# All-in-one_Starter_Kit_for_Pico_2_V1_3.net
KiCad netlist of a schematic drawn in EAGLE
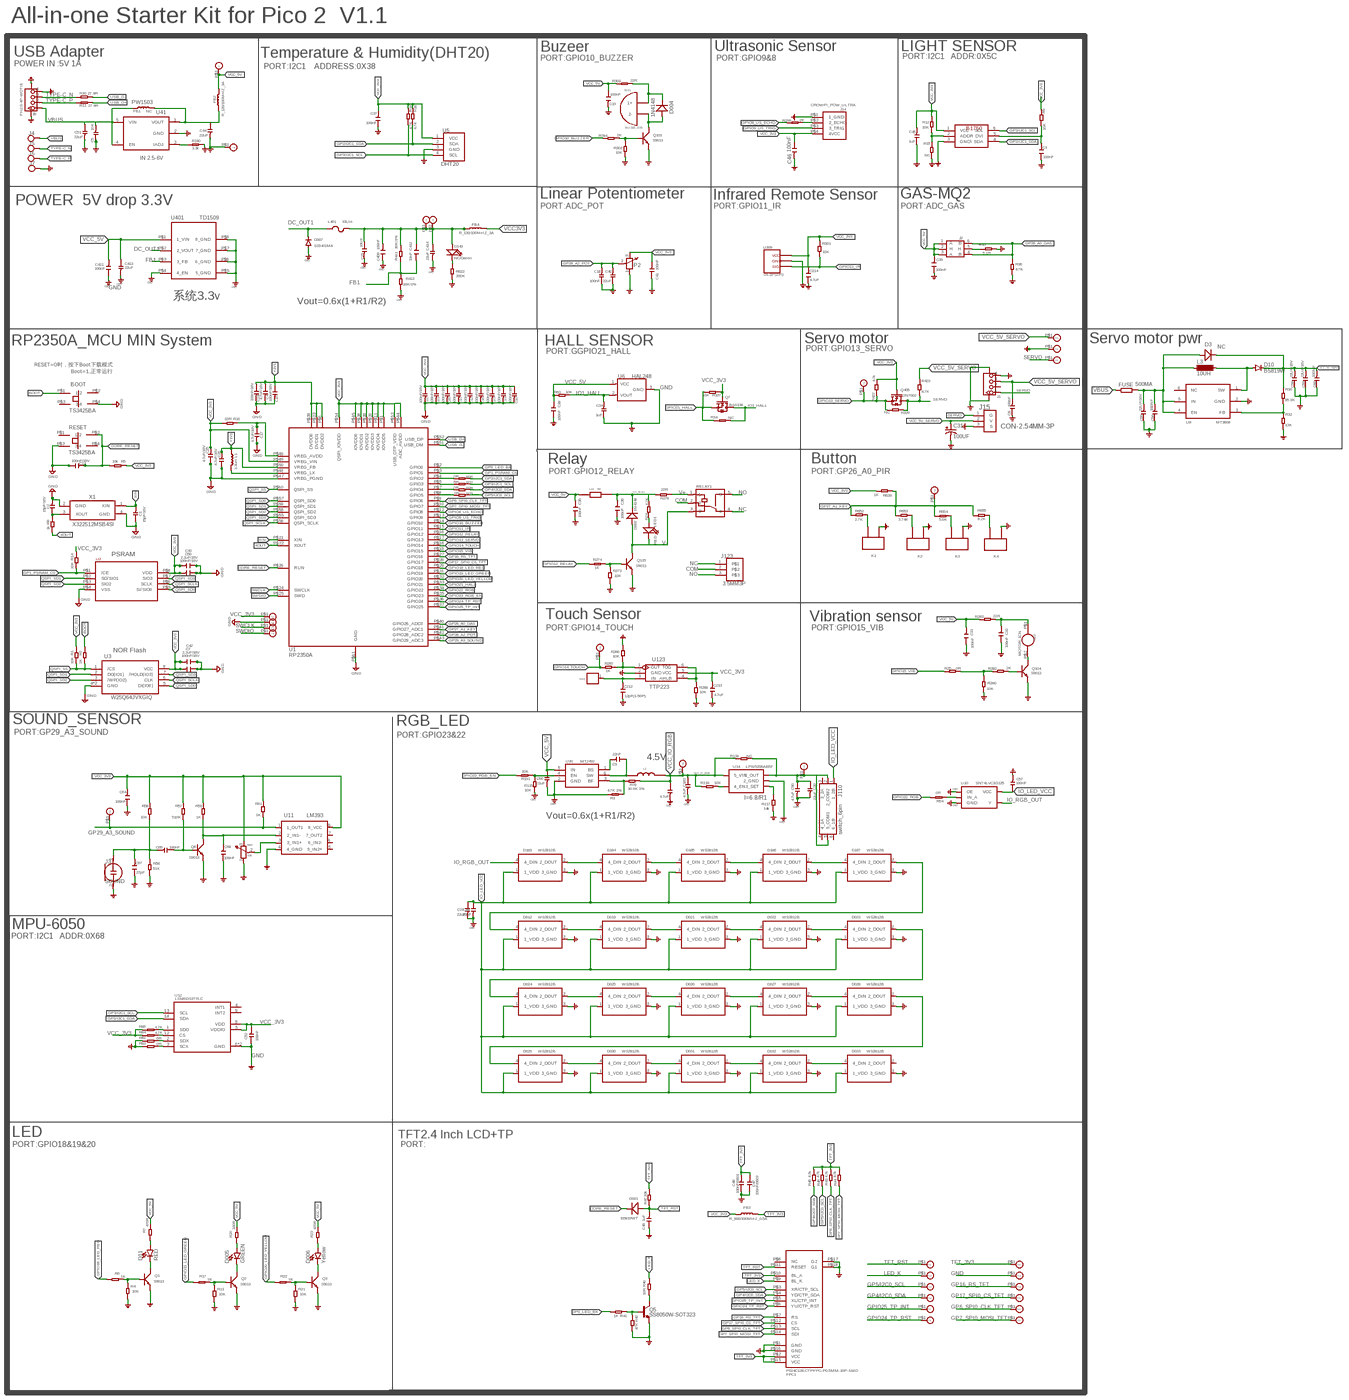
[diagram p0: schematic, sheet 1, overview]
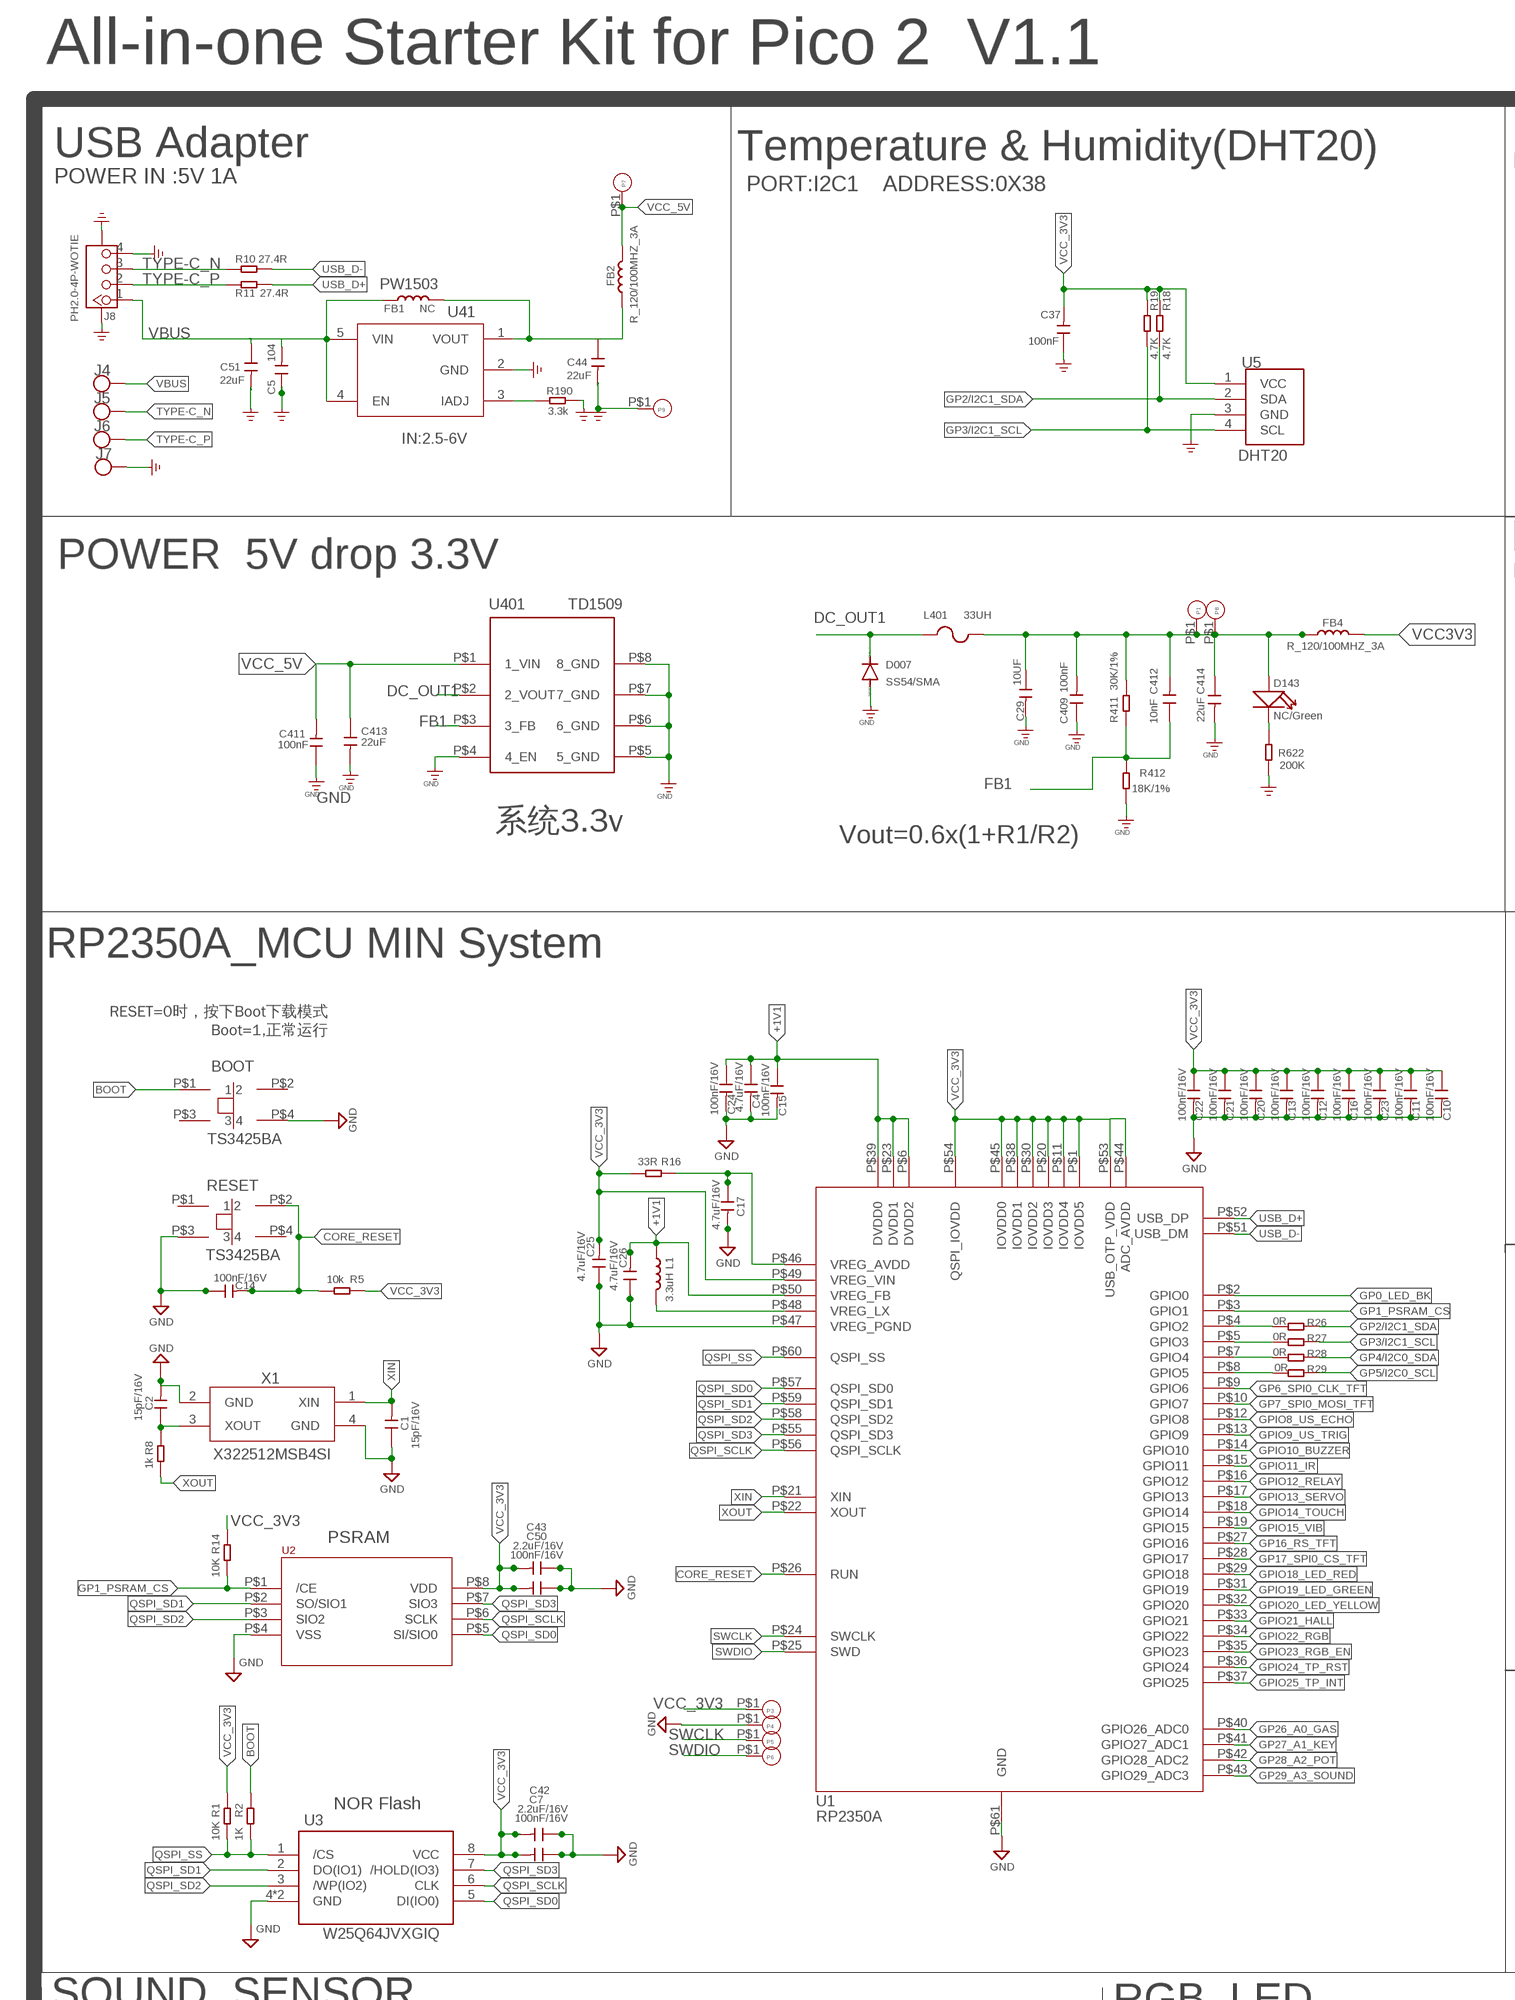
[diagram p1: schematic, sheet 1, part 1 of 4]
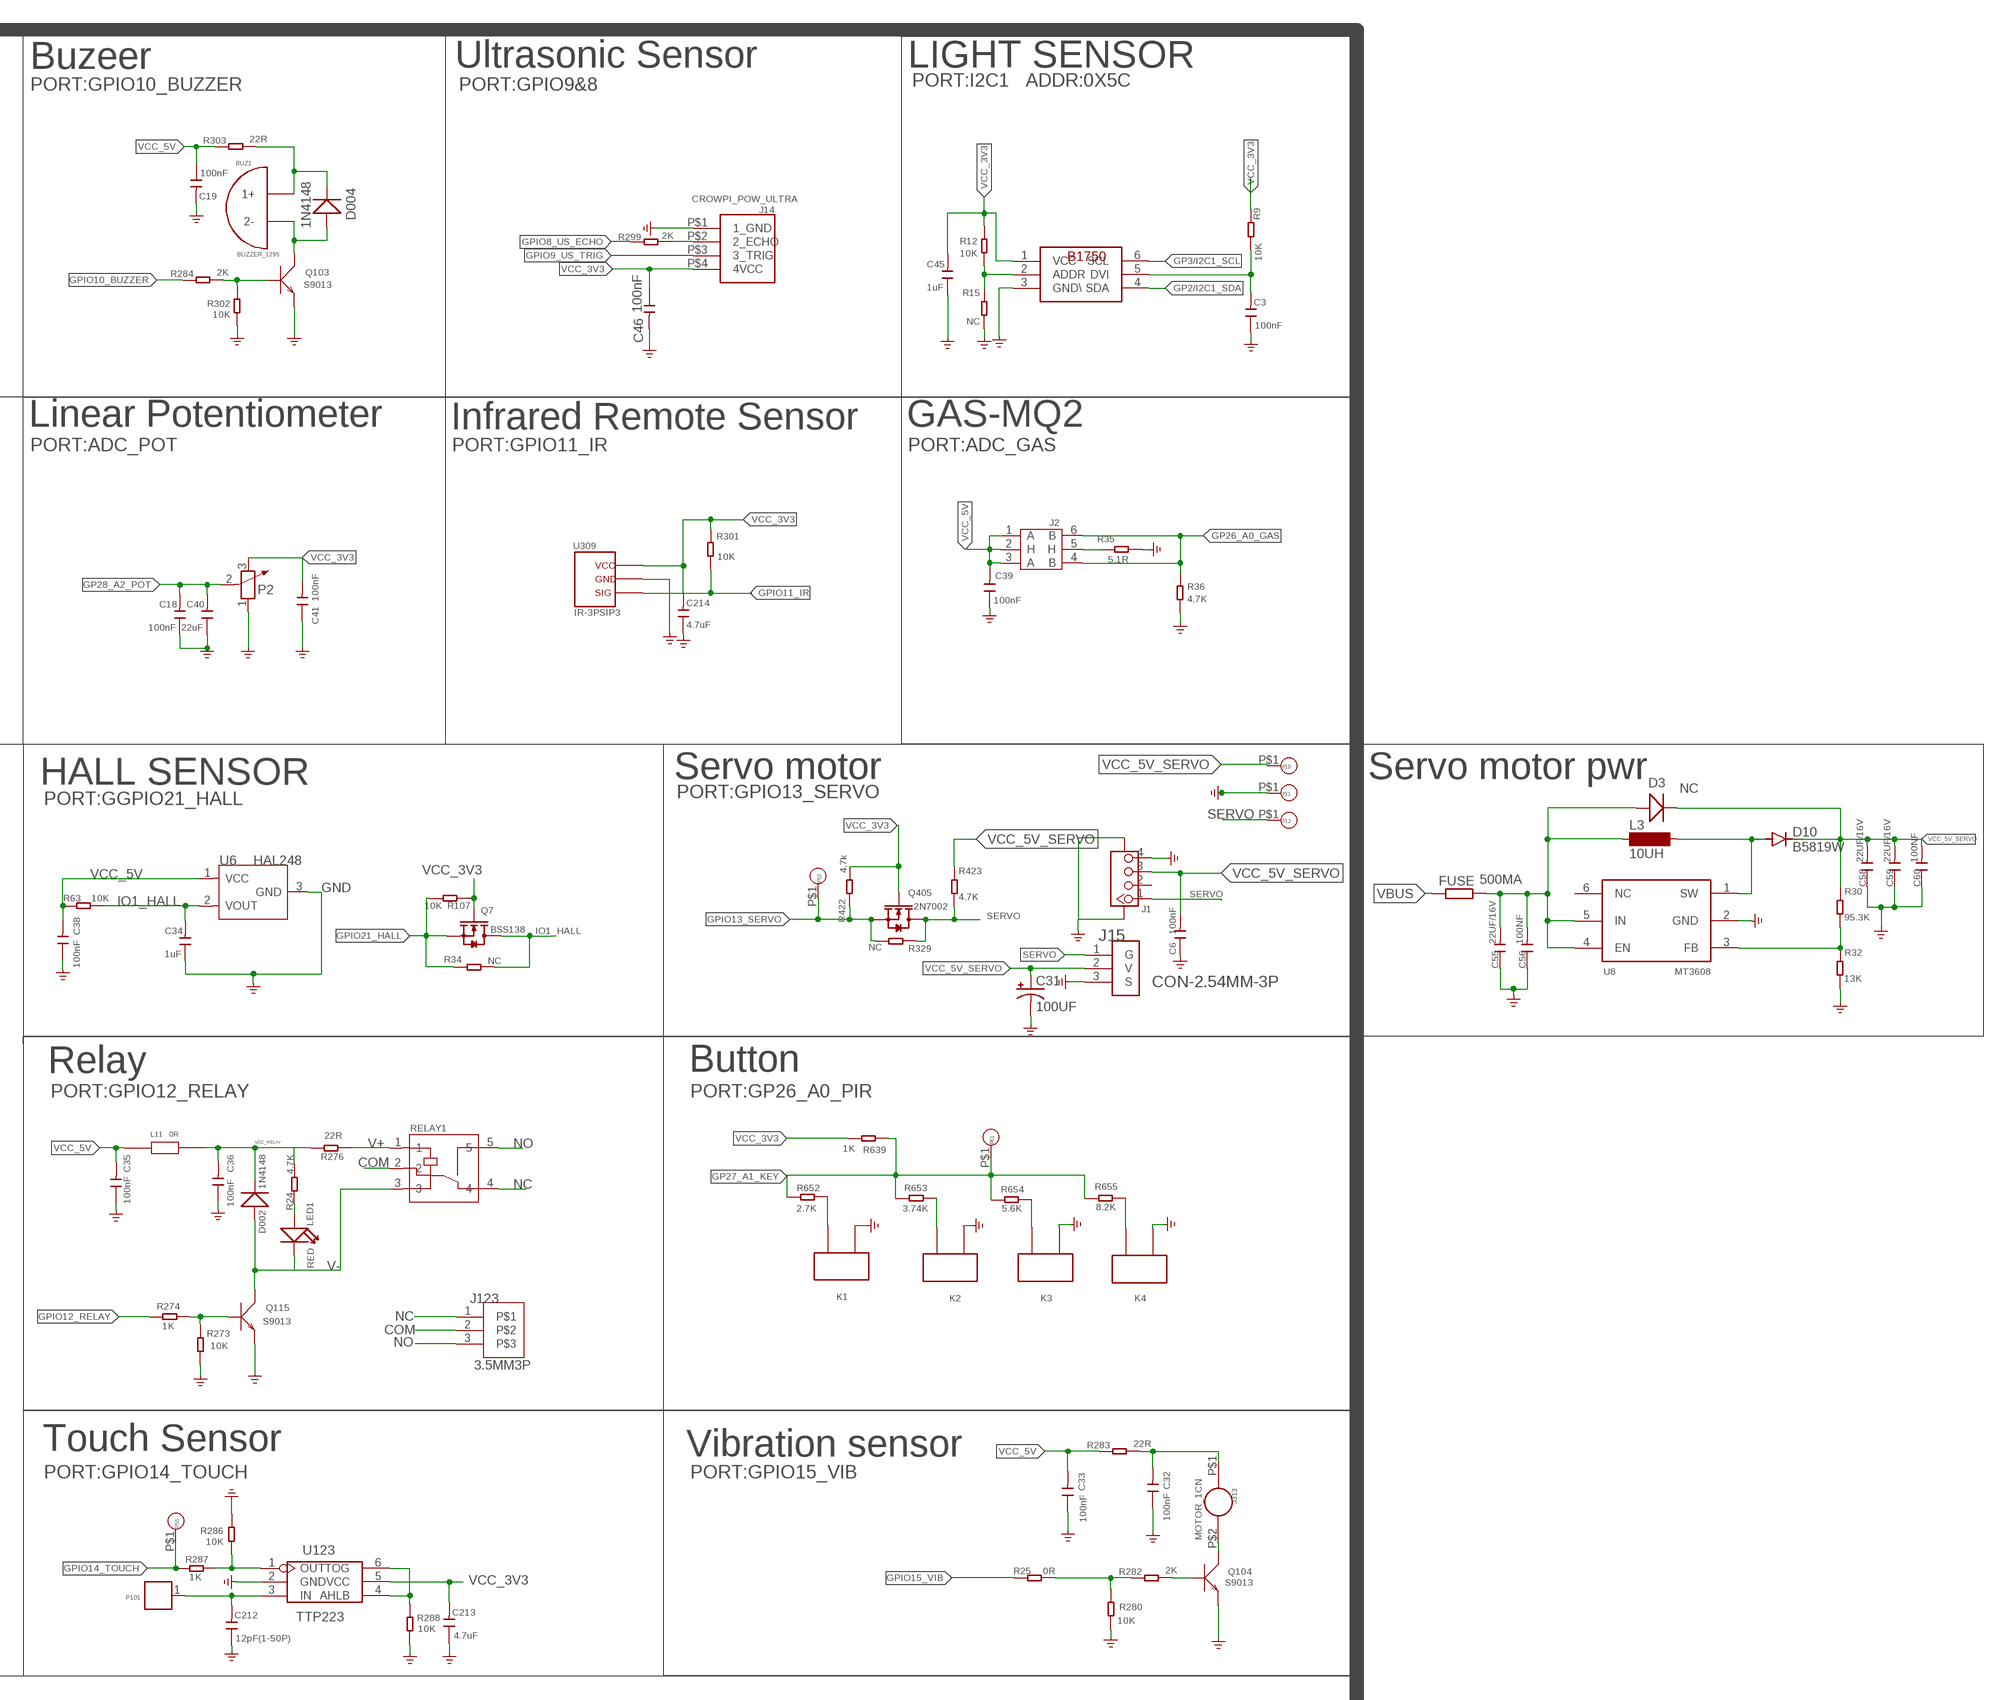
[diagram p2: schematic, sheet 1, part 2 of 4]
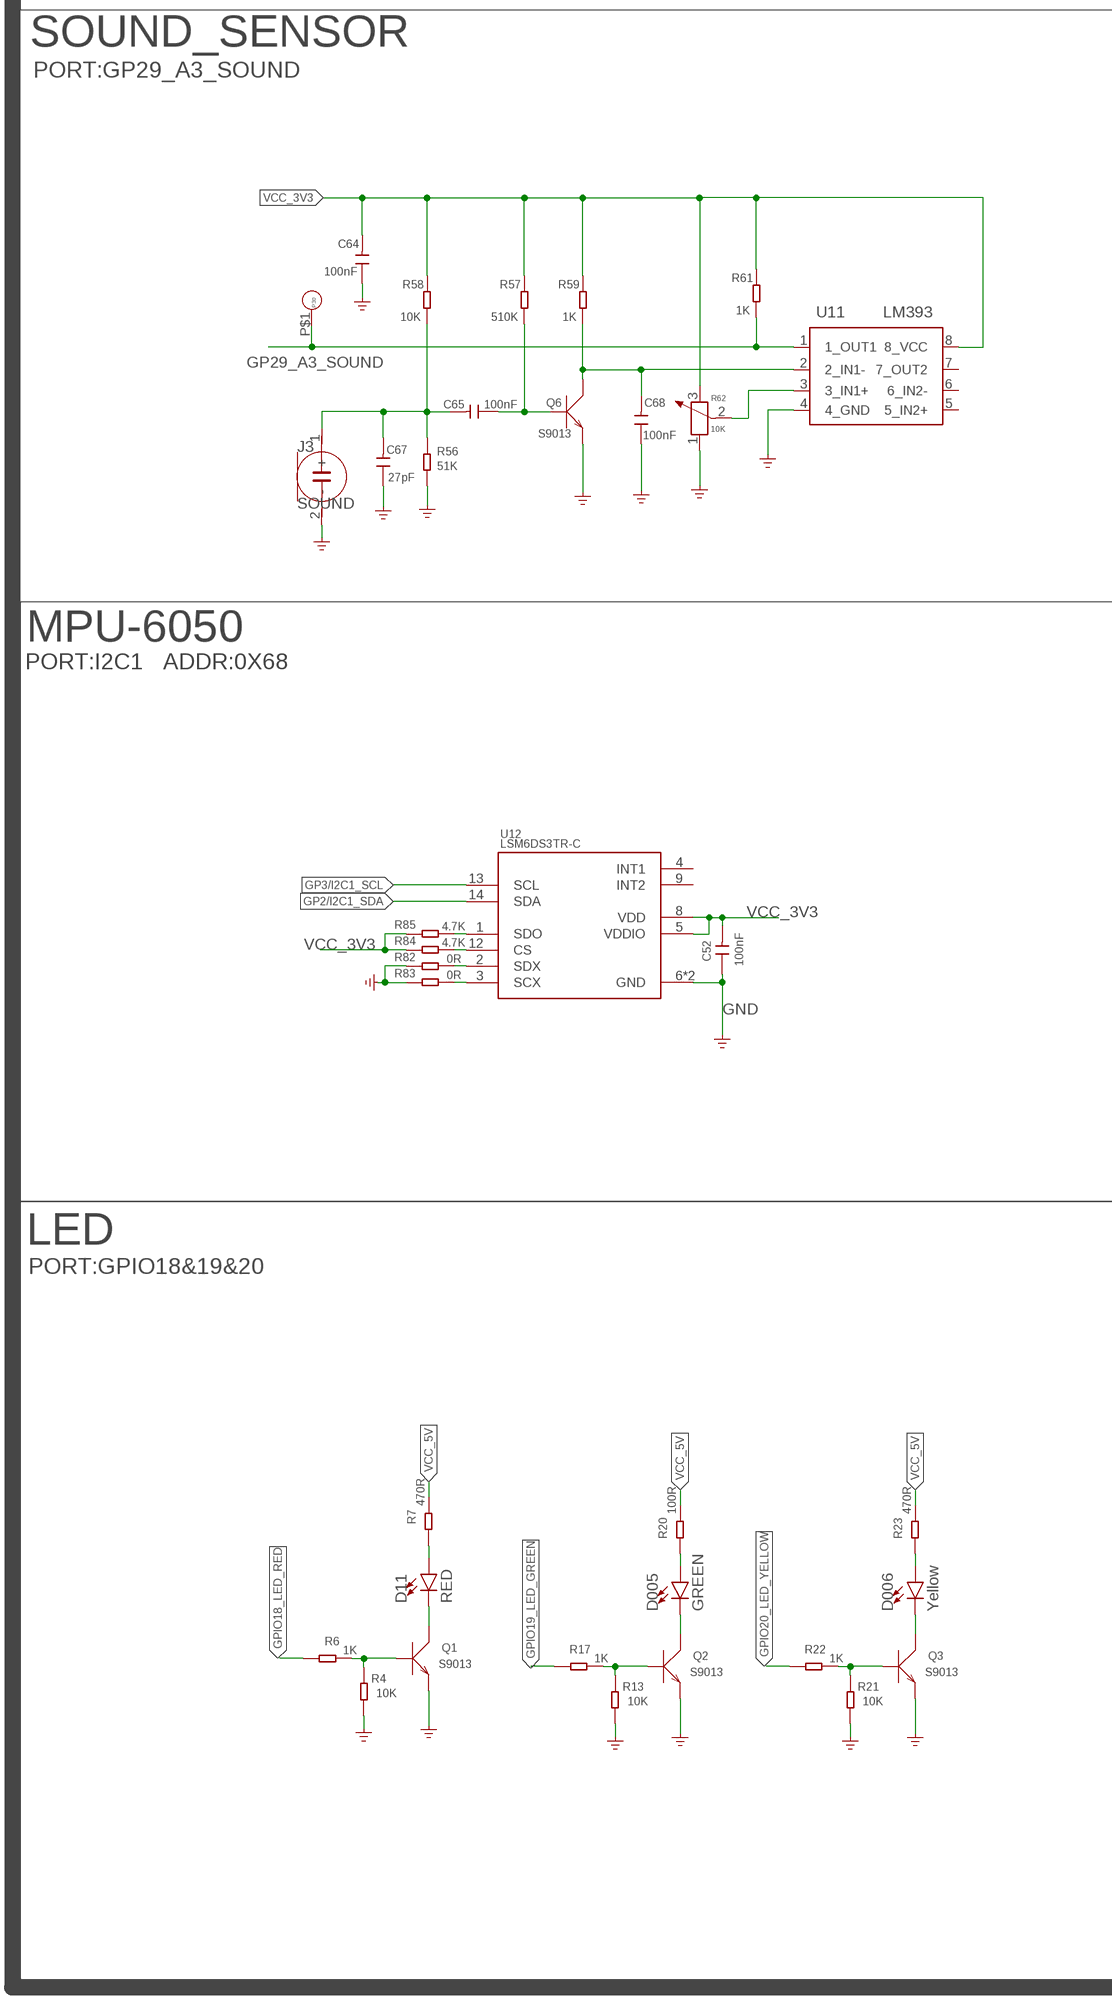
[diagram p3: schematic, sheet 1, part 3 of 4]
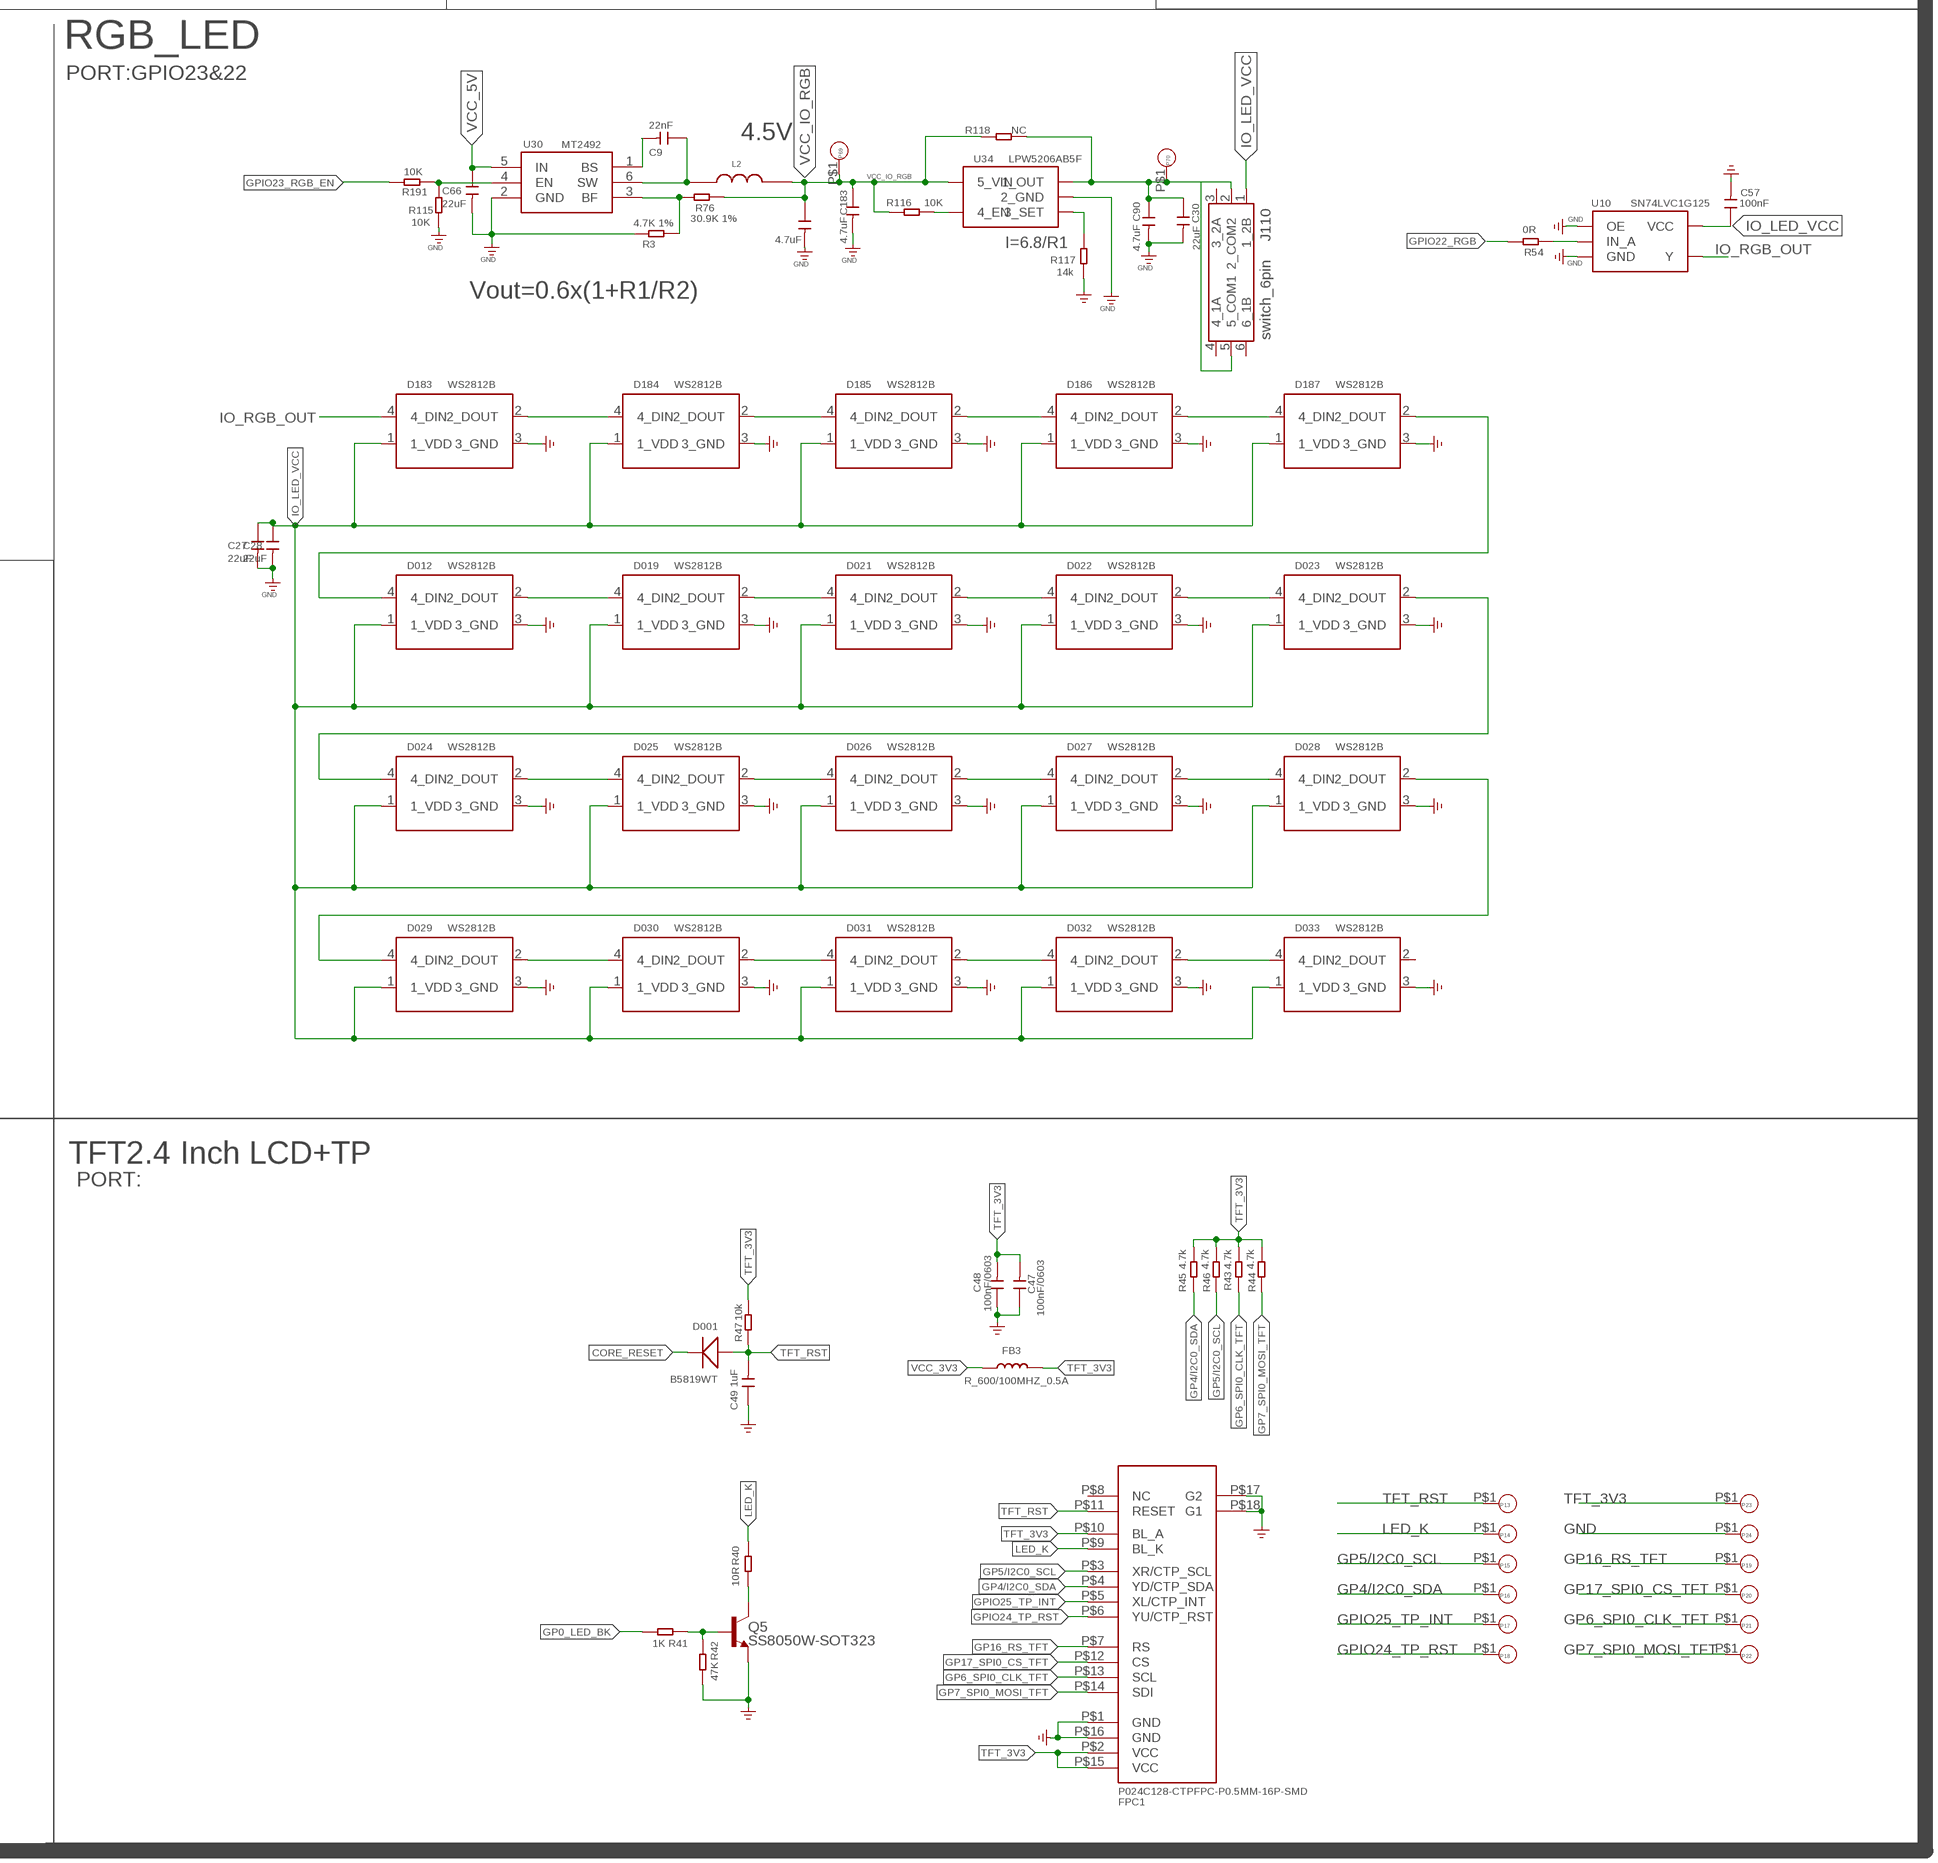
[diagram p4: schematic, sheet 1, part 4 of 4]

(export (version "E")
  (design (tool "Eeschema 10.0.6"))
  (components
    (comp (ref "BOOT")
      (value "TS3425BA")
      (footprint "eagle-import:SMD_KEY4.2_3._.2.5")
      (libsource (lib "eagle-import") (part "KEY"))
    )
    (comp (ref "BUZ1")
      (value "BUZZER_1295")
      (footprint "eagle-import:BUZZER-D12MM-DIP2")
      (libsource (lib "eagle-import") (part "BUZZERBUZZER_1295_DIP"))
    )
    (comp (ref "C1")
      (value "15pF/16V")
      (footprint "eagle-import:C0603")
      (libsource (lib "eagle-import") (part "CAPC0603"))
    )
    (comp (ref "C2")
      (value "15pF/16V")
      (footprint "eagle-import:C0603")
      (libsource (lib "eagle-import") (part "CAPC0603"))
    )
    (comp (ref "C3")
      (value "100nF")
      (footprint "eagle-import:C0603")
      (libsource (lib "eagle-import") (part "CAPC0603"))
    )
    (comp (ref "C4")
      (value "4.7uF/16V")
      (footprint "eagle-import:C0603")
      (libsource (lib "eagle-import") (part "CAPC0603"))
    )
    (comp (ref "C5")
      (value "104")
      (footprint "eagle-import:C0805")
      (libsource (lib "eagle-import") (part "CAPC0805"))
    )
    (comp (ref "C6")
      (value "100nF")
      (footprint "eagle-import:C0603")
      (libsource (lib "eagle-import") (part "CAPC0603"))
    )
    (comp (ref "C7")
      (value "100nF/16V")
      (footprint "eagle-import:C0603")
      (libsource (lib "eagle-import") (part "CAPC0603"))
    )
    (comp (ref "C8")
      (value "4.7uF")
      (footprint "eagle-import:C0603")
      (libsource (lib "eagle-import") (part "CAPC0603"))
    )
    (comp (ref "C9")
      (value "22nF")
      (footprint "eagle-import:C0603")
      (libsource (lib "eagle-import") (part "CAPC0603"))
    )
    (comp (ref "C10")
      (value "100nF/16V")
      (footprint "eagle-import:C0603")
      (libsource (lib "eagle-import") (part "CAPC0603"))
    )
    (comp (ref "C11")
      (value "100nF/16V")
      (footprint "eagle-import:C0603")
      (libsource (lib "eagle-import") (part "CAPC0603"))
    )
    (comp (ref "C12")
      (value "100nF/16V")
      (footprint "eagle-import:C0603")
      (libsource (lib "eagle-import") (part "CAPC0603"))
    )
    (comp (ref "C13")
      (value "100nF/16V")
      (footprint "eagle-import:C0603")
      (libsource (lib "eagle-import") (part "CAPC0603"))
    )
    (comp (ref "C14")
      (value "100nF/16V")
      (footprint "eagle-import:C0603")
      (libsource (lib "eagle-import") (part "CAPC0603"))
    )
    (comp (ref "C15")
      (value "100nF/16V")
      (footprint "eagle-import:C0603")
      (libsource (lib "eagle-import") (part "CAPC0603"))
    )
    (comp (ref "C16")
      (value "100nF/16V")
      (footprint "eagle-import:C0603")
      (libsource (lib "eagle-import") (part "CAPC0603"))
    )
    (comp (ref "C17")
      (value "4.7uF/16V")
      (footprint "eagle-import:C0603")
      (libsource (lib "eagle-import") (part "CAPC0603"))
    )
    (comp (ref "C18")
      (value "100nF")
      (footprint "eagle-import:C0603")
      (libsource (lib "eagle-import") (part "CAPC0603"))
    )
    (comp (ref "C19")
      (value "100nF")
      (footprint "eagle-import:C0603")
      (libsource (lib "eagle-import") (part "CAPC0603"))
    )
    (comp (ref "C20")
      (value "100nF/16V")
      (footprint "eagle-import:C0603")
      (libsource (lib "eagle-import") (part "CAPC0603"))
    )
    (comp (ref "C21")
      (value "100nF/16V")
      (footprint "eagle-import:C0603")
      (libsource (lib "eagle-import") (part "CAPC0603"))
    )
    (comp (ref "C22")
      (value "100nF/16V")
      (footprint "eagle-import:C0603")
      (libsource (lib "eagle-import") (part "CAPC0603"))
    )
    (comp (ref "C23")
      (value "100nF/16V")
      (footprint "eagle-import:C0603")
      (libsource (lib "eagle-import") (part "CAPC0603"))
    )
    (comp (ref "C24")
      (value "100nF/16V")
      (footprint "eagle-import:C0603")
      (libsource (lib "eagle-import") (part "CAPC0603"))
    )
    (comp (ref "C25")
      (value "4.7uF/16V")
      (footprint "eagle-import:C0603")
      (libsource (lib "eagle-import") (part "CAPC0603"))
    )
    (comp (ref "C26")
      (value "4.7uF/16V")
      (footprint "eagle-import:C0603")
      (libsource (lib "eagle-import") (part "CAPC0603"))
    )
    (comp (ref "C27")
      (value "22uF")
      (footprint "eagle-import:C0805")
      (libsource (lib "eagle-import") (part "CAPC0805"))
    )
    (comp (ref "C28")
      (value "22uF")
      (footprint "eagle-import:C0805")
      (libsource (lib "eagle-import") (part "CAPC0805"))
    )
    (comp (ref "C29")
      (value "10UF")
      (footprint "eagle-import:C0805")
      (libsource (lib "eagle-import") (part "CAPC0805"))
    )
    (comp (ref "C30")
      (value "22uF")
      (footprint "eagle-import:C0805")
      (libsource (lib "eagle-import") (part "CAPC0805"))
    )
    (comp (ref "C31")
      (value "100UF")
      (footprint "eagle-import:SANYO-OSCON_SMD_C6")
      (libsource (lib "eagle-import") (part "CPOL-USSANYO_SMD_C6"))
    )
    (comp (ref "C32")
      (value "100nF")
      (footprint "eagle-import:C0603")
      (libsource (lib "eagle-import") (part "CAPC0603"))
    )
    (comp (ref "C33")
      (value "100nF")
      (footprint "eagle-import:C0603")
      (libsource (lib "eagle-import") (part "CAPC0603"))
    )
    (comp (ref "C34")
      (value "1uF")
      (footprint "eagle-import:C0603")
      (libsource (lib "eagle-import") (part "CAPC0603"))
    )
    (comp (ref "C35")
      (value "100nF")
      (footprint "eagle-import:C0603")
      (libsource (lib "eagle-import") (part "CAPC0603"))
    )
    (comp (ref "C36")
      (value "100nF")
      (footprint "eagle-import:C0603")
      (libsource (lib "eagle-import") (part "CAPC0603"))
    )
    (comp (ref "C37")
      (value "100nF")
      (footprint "eagle-import:C0603")
      (libsource (lib "eagle-import") (part "CAPC0603"))
    )
    (comp (ref "C38")
      (value "100nF")
      (footprint "eagle-import:C0603")
      (libsource (lib "eagle-import") (part "CAPC0603"))
    )
    (comp (ref "C39")
      (value "100nF")
      (footprint "eagle-import:C0603")
      (libsource (lib "eagle-import") (part "CAPC0603"))
    )
    (comp (ref "C40")
      (value "22uF")
      (footprint "eagle-import:C0603")
      (libsource (lib "eagle-import") (part "CAPC0603"))
    )
    (comp (ref "C41")
      (value "100nF")
      (footprint "eagle-import:C0603")
      (libsource (lib "eagle-import") (part "CAPC0603"))
    )
    (comp (ref "C42")
      (value "2.2uF/16V")
      (footprint "eagle-import:C0603")
      (libsource (lib "eagle-import") (part "CAPC0603"))
    )
    (comp (ref "C43")
      (value "2.2uF/16V")
      (footprint "eagle-import:C0603")
      (libsource (lib "eagle-import") (part "CAPC0603"))
    )
    (comp (ref "C44")
      (value "22uF")
      (footprint "eagle-import:C0805")
      (libsource (lib "eagle-import") (part "CAPC0805"))
    )
    (comp (ref "C45")
      (value "1uF")
      (footprint "eagle-import:C0603")
      (libsource (lib "eagle-import") (part "CAPC0603"))
    )
    (comp (ref "C46")
      (value "100nF")
      (footprint "eagle-import:C0603")
      (libsource (lib "eagle-import") (part "CAPC0603"))
    )
    (comp (ref "C47")
      (value "100nF/0603")
      (footprint "eagle-import:C0603")
      (libsource (lib "eagle-import") (part "CAPC0603"))
    )
    (comp (ref "C48")
      (value "100nF/0603")
      (footprint "eagle-import:C0603")
      (libsource (lib "eagle-import") (part "CAPC0603"))
    )
    (comp (ref "C49")
      (value "1uF")
      (footprint "eagle-import:C0603")
      (libsource (lib "eagle-import") (part "CAPC0603"))
    )
    (comp (ref "C50")
      (value "100nF/16V")
      (footprint "eagle-import:C0603")
      (libsource (lib "eagle-import") (part "CAPC0603"))
    )
    (comp (ref "C51")
      (value "22uF")
      (footprint "eagle-import:C0805")
      (libsource (lib "eagle-import") (part "CAPC0805"))
    )
    (comp (ref "C52")
      (value "100nF")
      (footprint "eagle-import:C0603")
      (libsource (lib "eagle-import") (part "C-0603"))
    )
    (comp (ref "C55")
      (value "22UF/16V")
      (footprint "eagle-import:C0603")
      (libsource (lib "eagle-import") (part "CAP"))
    )
    (comp (ref "C56")
      (value "100NF")
      (footprint "eagle-import:C0603")
      (libsource (lib "eagle-import") (part "CAP"))
    )
    (comp (ref "C57")
      (value "100nF")
      (footprint "eagle-import:C0603")
      (libsource (lib "eagle-import") (part "CAPC0603"))
    )
    (comp (ref "C58")
      (value "22UF/16V")
      (footprint "eagle-import:C0603")
      (libsource (lib "eagle-import") (part "CAP"))
    )
    (comp (ref "C59")
      (value "22UF/16V")
      (footprint "eagle-import:C0603")
      (libsource (lib "eagle-import") (part "CAP"))
    )
    (comp (ref "C60")
      (value "100NF")
      (footprint "eagle-import:C0603")
      (libsource (lib "eagle-import") (part "CAP"))
    )
    (comp (ref "C64")
      (value "100nF")
      (footprint "eagle-import:C0603")
      (libsource (lib "eagle-import") (part "CAPC0603"))
    )
    (comp (ref "C65")
      (value "100nF")
      (footprint "eagle-import:C0603")
      (libsource (lib "eagle-import") (part "CAPC0603"))
    )
    (comp (ref "C66")
      (value "22uF")
      (footprint "eagle-import:C0805")
      (libsource (lib "eagle-import") (part "CAPC0805"))
    )
    (comp (ref "C67")
      (value "27pF")
      (footprint "eagle-import:C0603")
      (libsource (lib "eagle-import") (part "CAPC0603"))
    )
    (comp (ref "C68")
      (value "100nF")
      (footprint "eagle-import:C0603")
      (libsource (lib "eagle-import") (part "CAPC0603"))
    )
    (comp (ref "C90")
      (value "4.7uF")
      (footprint "eagle-import:C0603")
      (libsource (lib "eagle-import") (part "CAPC0603"))
    )
    (comp (ref "C183")
      (value "4.7uF")
      (footprint "eagle-import:C0603")
      (libsource (lib "eagle-import") (part "CAPC0603"))
    )
    (comp (ref "C212")
      (value "12pF(1-50P)")
      (footprint "eagle-import:C0603")
      (libsource (lib "eagle-import") (part "CAPC0603"))
    )
    (comp (ref "C213")
      (value "4.7uF")
      (footprint "eagle-import:C0603")
      (libsource (lib "eagle-import") (part "CAPC0603"))
    )
    (comp (ref "C214")
      (value "4.7uF")
      (footprint "eagle-import:C0603")
      (libsource (lib "eagle-import") (part "CAPC0603"))
    )
    (comp (ref "C409")
      (value "100nF")
      (footprint "eagle-import:C0603")
      (libsource (lib "eagle-import") (part "CAPC0603"))
    )
    (comp (ref "C411")
      (value "100nF")
      (footprint "eagle-import:C0603")
      (libsource (lib "eagle-import") (part "CAPC0603"))
    )
    (comp (ref "C412")
      (value "10nF")
      (footprint "eagle-import:C0603")
      (libsource (lib "eagle-import") (part "CAPC0603"))
    )
    (comp (ref "C413")
      (value "22uF")
      (footprint "eagle-import:C0805")
      (libsource (lib "eagle-import") (part "CAPC0805"))
    )
    (comp (ref "C414")
      (value "22uF")
      (footprint "eagle-import:C0805")
      (libsource (lib "eagle-import") (part "CAPC0805"))
    )
    (comp (ref "D001")
      (value "B5819WT")
      (footprint "eagle-import:D_SOD523")
      (libsource (lib "eagle-import") (part "DIODE0603"))
    )
    (comp (ref "D002")
      (value "1N4148")
      (footprint "eagle-import:D_SOD123")
      (libsource (lib "eagle-import") (part "Crowtail_Starter_DIODE1206"))
    )
    (comp (ref "D3")
      (value "NC")
      (footprint "eagle-import:D_SOD123FL")
      (libsource (lib "eagle-import") (part "DIODE"))
    )
    (comp (ref "D004")
      (value "1N4148")
      (footprint "eagle-import:D_SOD123")
      (libsource (lib "eagle-import") (part "Crowtail_Starter_DIODE1206"))
    )
    (comp (ref "D005")
      (value "GREEN")
      (footprint "eagle-import:LED-8MM")
      (libsource (lib "eagle-import") (part "LED"))
    )
    (comp (ref "D006")
      (value "Yellow")
      (footprint "eagle-import:LED-8MM")
      (libsource (lib "eagle-import") (part "LED"))
    )
    (comp (ref "D007")
      (value "SS54/SMA")
      (footprint "eagle-import:DIODE_DO-214AC")
      (libsource (lib "eagle-import") (part "DIODE_DIODE-DO-214AC"))
    )
    (comp (ref "D10")
      (value "B5819W")
      (footprint "eagle-import:SOD-123_MINI-SMA")
      (libsource (lib "eagle-import") (part "CGRM400-G1"))
    )
    (comp (ref "D11")
      (value "RED")
      (footprint "eagle-import:LED-8MM")
      (libsource (lib "eagle-import") (part "LED"))
    )
    (comp (ref "D012")
      (value "WS2812B")
      (footprint "eagle-import:LED_RGB_WS2812_3535")
      (libsource (lib "eagle-import") (part "LED_RGB_WS2812_3535"))
    )
    (comp (ref "D019")
      (value "WS2812B")
      (footprint "eagle-import:LED_RGB_WS2812_3535")
      (libsource (lib "eagle-import") (part "LED_RGB_WS2812_3535"))
    )
    (comp (ref "D021")
      (value "WS2812B")
      (footprint "eagle-import:LED_RGB_WS2812_3535")
      (libsource (lib "eagle-import") (part "LED_RGB_WS2812_3535"))
    )
    (comp (ref "D022")
      (value "WS2812B")
      (footprint "eagle-import:LED_RGB_WS2812_3535")
      (libsource (lib "eagle-import") (part "LED_RGB_WS2812_3535"))
    )
    (comp (ref "D023")
      (value "WS2812B")
      (footprint "eagle-import:LED_RGB_WS2812_3535")
      (libsource (lib "eagle-import") (part "LED_RGB_WS2812_3535"))
    )
    (comp (ref "D024")
      (value "WS2812B")
      (footprint "eagle-import:LED_RGB_WS2812_3535")
      (libsource (lib "eagle-import") (part "LED_RGB_WS2812_3535"))
    )
    (comp (ref "D025")
      (value "WS2812B")
      (footprint "eagle-import:LED_RGB_WS2812_3535")
      (libsource (lib "eagle-import") (part "LED_RGB_WS2812_3535"))
    )
    (comp (ref "D026")
      (value "WS2812B")
      (footprint "eagle-import:LED_RGB_WS2812_3535")
      (libsource (lib "eagle-import") (part "LED_RGB_WS2812_3535"))
    )
    (comp (ref "D027")
      (value "WS2812B")
      (footprint "eagle-import:LED_RGB_WS2812_3535")
      (libsource (lib "eagle-import") (part "LED_RGB_WS2812_3535"))
    )
    (comp (ref "D028")
      (value "WS2812B")
      (footprint "eagle-import:LED_RGB_WS2812_3535")
      (libsource (lib "eagle-import") (part "LED_RGB_WS2812_3535"))
    )
    (comp (ref "D029")
      (value "WS2812B")
      (footprint "eagle-import:LED_RGB_WS2812_3535")
      (libsource (lib "eagle-import") (part "LED_RGB_WS2812_3535"))
    )
    (comp (ref "D030")
      (value "WS2812B")
      (footprint "eagle-import:LED_RGB_WS2812_3535")
      (libsource (lib "eagle-import") (part "LED_RGB_WS2812_3535"))
    )
    (comp (ref "D031")
      (value "WS2812B")
      (footprint "eagle-import:LED_RGB_WS2812_3535")
      (libsource (lib "eagle-import") (part "LED_RGB_WS2812_3535"))
    )
    (comp (ref "D032")
      (value "WS2812B")
      (footprint "eagle-import:LED_RGB_WS2812_3535")
      (libsource (lib "eagle-import") (part "LED_RGB_WS2812_3535"))
    )
    (comp (ref "D033")
      (value "WS2812B")
      (footprint "eagle-import:LED_RGB_WS2812_3535")
      (libsource (lib "eagle-import") (part "LED_RGB_WS2812_3535"))
    )
    (comp (ref "D143")
      (value "NC/Green")
      (footprint "eagle-import:LED_0603_SMT")
      (libsource (lib "eagle-import") (part "LED_0603_SMT"))
    )
    (comp (ref "D183")
      (value "WS2812B")
      (footprint "eagle-import:LED_RGB_WS2812_3535")
      (libsource (lib "eagle-import") (part "LED_RGB_WS2812_3535"))
    )
    (comp (ref "D184")
      (value "WS2812B")
      (footprint "eagle-import:LED_RGB_WS2812_3535")
      (libsource (lib "eagle-import") (part "LED_RGB_WS2812_3535"))
    )
    (comp (ref "D185")
      (value "WS2812B")
      (footprint "eagle-import:LED_RGB_WS2812_3535")
      (libsource (lib "eagle-import") (part "LED_RGB_WS2812_3535"))
    )
    (comp (ref "D186")
      (value "WS2812B")
      (footprint "eagle-import:LED_RGB_WS2812_3535")
      (libsource (lib "eagle-import") (part "LED_RGB_WS2812_3535"))
    )
    (comp (ref "D187")
      (value "WS2812B")
      (footprint "eagle-import:LED_RGB_WS2812_3535")
      (libsource (lib "eagle-import") (part "LED_RGB_WS2812_3535"))
    )
    (comp (ref "FB1")
      (value "NC")
      (footprint "eagle-import:L0805")
      (libsource (lib "eagle-import") (part "R_120/100MHZ_3A"))
    )
    (comp (ref "FB2")
      (value "R_120/100MHZ_3A")
      (footprint "eagle-import:L0805")
      (libsource (lib "eagle-import") (part "R_120/100MHZ_3A"))
    )
    (comp (ref "FB3")
      (value "R_600/100MHZ_0.5A")
      (footprint "eagle-import:L0603")
      (libsource (lib "eagle-import") (part "R_600/100MHZ_0.5A"))
    )
    (comp (ref "FB4")
      (value "R_120/100MHZ_3A")
      (footprint "eagle-import:L0805")
      (libsource (lib "eagle-import") (part "R_120/100MHZ_3A"))
    )
    (comp (ref "FPC1")
      (value "P024C128-CTPFPC-P0.5MM-16P-SMD")
      (footprint "eagle-import:FPC-P0.5MM-16P-SMD")
      (libsource (lib "eagle-import") (part "P024C128-CTPFPC-P0.5MM-16P-SMD"))
    )
    (comp (ref "FUSE")
      (value "500MA")
      (footprint "eagle-import:R0805")
      (libsource (lib "eagle-import") (part "R-EU_R0805"))
    )
    (comp (ref "J1")
      (value "A_XBJ_CONNECTOR_TWIG-4P-2.0-SMD-FEMALE-REINFORCE90D")
      (footprint "eagle-import:A_XBJ_CONNECTOR_4P-SMD-2.0-90D")
      (libsource (lib "eagle-import") (part "A_XBJ_CONNECTOR_TWIG-4P-2.0-SMD-FEMALE-REINFORCE90D"))
    )
    (comp (ref "J2")
      (value "MQ-SOCKET")
      (footprint "eagle-import:MQ2")
      (libsource (lib "eagle-import") (part "MQ-SOCKET"))
    )
    (comp (ref "J3")
      (value "SOUND")
      (footprint "eagle-import:TEMPLATE_2P-D8.9MM")
      (libsource (lib "eagle-import") (part "TEMPLATE_MICROPHONE"))
    )
    (comp (ref "J4")
      (value "TP-SMDTP-SMD-2X4MM")
      (footprint "eagle-import:TP-SMD-2X4MM")
      (libsource (lib "eagle-import") (part "TP-SMDTP-SMD-2X4MM"))
    )
    (comp (ref "J5")
      (value "TP-SMDTP-SMD-2X4MM")
      (footprint "eagle-import:TP-SMD-2X4MM")
      (libsource (lib "eagle-import") (part "TP-SMDTP-SMD-2X4MM"))
    )
    (comp (ref "J6")
      (value "TP-SMDTP-SMD-2X4MM")
      (footprint "eagle-import:TP-SMD-2X4MM")
      (libsource (lib "eagle-import") (part "TP-SMDTP-SMD-2X4MM"))
    )
    (comp (ref "J7")
      (value "TP-SMDTP-SMD-2X4MM")
      (footprint "eagle-import:TP-SMD-2X4MM")
      (libsource (lib "eagle-import") (part "TP-SMDTP-SMD-2X4MM"))
    )
    (comp (ref "J8")
      (value "PH2.0-4P-WOTIE")
      (footprint "eagle-import:PH2.0-4P")
      (libsource (lib "eagle-import") (part "PH2.0-4P-WOTIE"))
    )
    (comp (ref "J14")
      (value "CROWPI_POW_ULTRA")
      (footprint "eagle-import:CROWPI_POW_ULTRA")
      (libsource (lib "eagle-import") (part "CROWPI_POW_ULTRA"))
    )
    (comp (ref "J15")
      (value "CON-2.54MM-3P")
      (footprint "eagle-import:CON-PZ-2.54MM-1_3P-WT")
      (libsource (lib "eagle-import") (part "CON-2.54MM-13P-WT-SG90"))
    )
    (comp (ref "J110")
      (value "switch_6pin")
      (footprint "eagle-import:SWITCH_6PIN_2P")
      (libsource (lib "eagle-import") (part "SWITCH_6PIN_2P"))
    )
    (comp (ref "J123")
      (value "3.5MM3P")
      (footprint "eagle-import:3.5MM_3P")
      (libsource (lib "eagle-import") (part "3.5MM3P"))
    )
    (comp (ref "J313")
      (value "MOTOR_1CN")
      (footprint "eagle-import:MOTOR_1CM")
      (libsource (lib "eagle-import") (part "MOTOR_1CN"))
    )
    (comp (ref "K1")
      (value "BUTTON_2P")
      (footprint "eagle-import:BUTTON_2P")
      (libsource (lib "eagle-import") (part "BUTTON_2P"))
    )
    (comp (ref "K2")
      (value "BUTTON_2P")
      (footprint "eagle-import:BUTTON_2P")
      (libsource (lib "eagle-import") (part "BUTTON_2P"))
    )
    (comp (ref "K3")
      (value "BUTTON_2P")
      (footprint "eagle-import:BUTTON_2P")
      (libsource (lib "eagle-import") (part "BUTTON_2P"))
    )
    (comp (ref "K4")
      (value "BUTTON_2P")
      (footprint "eagle-import:BUTTON_2P")
      (libsource (lib "eagle-import") (part "BUTTON_2P"))
    )
    (comp (ref "L1")
      (value "3.3uH")
      (footprint "eagle-import:SMD,1.6X2MM")
      (libsource (lib "eagle-import") (part "FTC201610S3R3MBCA"))
    )
    (comp (ref "L2")
      (value "CD32_950MA")
      (footprint "eagle-import:CD32")
      (libsource (lib "eagle-import") (part "CD32_950MA"))
    )
    (comp (ref "L3")
      (value "10UH")
      (footprint "eagle-import:MS42")
      (libsource (lib "eagle-import") (part "MS42"))
    )
    (comp (ref "L11")
      (value "0R")
      (footprint "eagle-import:201209")
      (libsource (lib "eagle-import") (part "CMP201209UD1R0MT201209"))
    )
    (comp (ref "L401")
      (value "33UH")
      (footprint "eagle-import:L773")
      (libsource (lib "eagle-import") (part "L-773"))
    )
    (comp (ref "LED1")
      (value "RED")
      (footprint "eagle-import:DISCRETE_LED-0603")
      (libsource (lib "eagle-import") (part "DISCRETE_LED0603"))
    )
    (comp (ref "P1")
      (value "PADPAD-1.0MM")
      (footprint "eagle-import:PAD-1.0MM")
      (libsource (lib "eagle-import") (part "PADPAD-1.0MM"))
    )
    (comp (ref "P2")
      (value "R-POTENTIOMETER")
      (footprint "eagle-import:3P-SQUA-45.6X10X5.8H")
      (libsource (lib "eagle-import") (part "R-POTENTIOMETER"))
    )
    (comp (ref "P3")
      (value "PADPAD-1.0MM")
      (footprint "eagle-import:PAD-1.0MM")
      (libsource (lib "eagle-import") (part "PADPAD-1.0MM"))
    )
    (comp (ref "P4")
      (value "PADPAD-1.0MM")
      (footprint "eagle-import:PAD-1.0MM")
      (libsource (lib "eagle-import") (part "PADPAD-1.0MM"))
    )
    (comp (ref "P5")
      (value "PADPAD-1.0MM")
      (footprint "eagle-import:PAD-1.0MM")
      (libsource (lib "eagle-import") (part "PADPAD-1.0MM"))
    )
    (comp (ref "P6")
      (value "PADPAD-1.0MM")
      (footprint "eagle-import:PAD-1.0MM")
      (libsource (lib "eagle-import") (part "PADPAD-1.0MM"))
    )
    (comp (ref "P7")
      (value "PADPAD-1.0MM")
      (footprint "eagle-import:PAD-1.0MM")
      (libsource (lib "eagle-import") (part "PADPAD-1.0MM"))
    )
    (comp (ref "P8")
      (value "PADPAD-1.0MM")
      (footprint "eagle-import:PAD-1.0MM")
      (libsource (lib "eagle-import") (part "PADPAD-1.0MM"))
    )
    (comp (ref "P9")
      (value "PADPAD-1.0MM")
      (footprint "eagle-import:PAD-1.0MM")
      (libsource (lib "eagle-import") (part "PADPAD-1.0MM"))
    )
    (comp (ref "P10")
      (value "PADPAD-1.0MM")
      (footprint "eagle-import:PAD-1.0MM")
      (libsource (lib "eagle-import") (part "PADPAD-1.0MM"))
    )
    (comp (ref "P11")
      (value "PADPAD-1.0MM")
      (footprint "eagle-import:PAD-1.0MM")
      (libsource (lib "eagle-import") (part "PADPAD-1.0MM"))
    )
    (comp (ref "P12")
      (value "PADPAD-1.0MM")
      (footprint "eagle-import:PAD-1.0MM")
      (libsource (lib "eagle-import") (part "PADPAD-1.0MM"))
    )
    (comp (ref "P13")
      (value "PADPAD-1.0MM")
      (footprint "eagle-import:PAD-1.0MM")
      (libsource (lib "eagle-import") (part "PADPAD-1.0MM"))
    )
    (comp (ref "P14")
      (value "PADPAD-1.0MM")
      (footprint "eagle-import:PAD-1.0MM")
      (libsource (lib "eagle-import") (part "PADPAD-1.0MM"))
    )
    (comp (ref "P15")
      (value "PADPAD-1.0MM")
      (footprint "eagle-import:PAD-1.0MM")
      (libsource (lib "eagle-import") (part "PADPAD-1.0MM"))
    )
    (comp (ref "P16")
      (value "PADPAD-1.0MM")
      (footprint "eagle-import:PAD-1.0MM")
      (libsource (lib "eagle-import") (part "PADPAD-1.0MM"))
    )
    (comp (ref "P17")
      (value "PADPAD-1.0MM")
      (footprint "eagle-import:PAD-1.0MM")
      (libsource (lib "eagle-import") (part "PADPAD-1.0MM"))
    )
    (comp (ref "P18")
      (value "PADPAD-1.0MM")
      (footprint "eagle-import:PAD-1.0MM")
      (libsource (lib "eagle-import") (part "PADPAD-1.0MM"))
    )
    (comp (ref "P19")
      (value "PADPAD-1.0MM")
      (footprint "eagle-import:PAD-1.0MM")
      (libsource (lib "eagle-import") (part "PADPAD-1.0MM"))
    )
    (comp (ref "P20")
      (value "PADPAD-1.0MM")
      (footprint "eagle-import:PAD-1.0MM")
      (libsource (lib "eagle-import") (part "PADPAD-1.0MM"))
    )
    (comp (ref "P21")
      (value "PADPAD-1.0MM")
      (footprint "eagle-import:PAD-1.0MM")
      (libsource (lib "eagle-import") (part "PADPAD-1.0MM"))
    )
    (comp (ref "P22")
      (value "PADPAD-1.0MM")
      (footprint "eagle-import:PAD-1.0MM")
      (libsource (lib "eagle-import") (part "PADPAD-1.0MM"))
    )
    (comp (ref "P23")
      (value "PADPAD-1.0MM")
      (footprint "eagle-import:PAD-1.0MM")
      (libsource (lib "eagle-import") (part "PADPAD-1.0MM"))
    )
    (comp (ref "P24")
      (value "PADPAD-1.0MM")
      (footprint "eagle-import:PAD-1.0MM")
      (libsource (lib "eagle-import") (part "PADPAD-1.0MM"))
    )
    (comp (ref "P30")
      (value "PADPAD-1.0MM")
      (footprint "eagle-import:PAD-1.0MM")
      (libsource (lib "eagle-import") (part "PADPAD-1.0MM"))
    )
    (comp (ref "P53")
      (value "PADPAD-1.0MM")
      (footprint "eagle-import:PAD-1.0MM")
      (libsource (lib "eagle-import") (part "PADPAD-1.0MM"))
    )
    (comp (ref "P55")
      (value "PADPAD-1.0MM")
      (footprint "eagle-import:PAD-1.0MM")
      (libsource (lib "eagle-import") (part "PADPAD-1.0MM"))
    )
    (comp (ref "P61")
      (value "PADPAD-1.0MM")
      (footprint "eagle-import:PAD-1.0MM")
      (libsource (lib "eagle-import") (part "PADPAD-1.0MM"))
    )
    (comp (ref "P69")
      (value "PADPAD-1.0MM")
      (footprint "eagle-import:PAD-1.0MM")
      (libsource (lib "eagle-import") (part "PADPAD-1.0MM"))
    )
    (comp (ref "P70")
      (value "PADPAD-1.0MM")
      (footprint "eagle-import:PAD-1.0MM")
      (libsource (lib "eagle-import") (part "PADPAD-1.0MM"))
    )
    (comp (ref "P101")
      (value "KEY")
      (footprint "eagle-import:1P-D450")
      (libsource (lib "eagle-import") (part "PAD'D450MIL'"))
    )
    (comp (ref "Q1")
      (value "S9013")
      (footprint "eagle-import:SOT23@1")
      (libsource (lib "eagle-import") (part "TRANSISTOR-NPN-SOT23"))
    )
    (comp (ref "Q2")
      (value "S9013")
      (footprint "eagle-import:SOT23@1")
      (libsource (lib "eagle-import") (part "TRANSISTOR-NPN-SOT23"))
    )
    (comp (ref "Q3")
      (value "S9013")
      (footprint "eagle-import:SOT23@1")
      (libsource (lib "eagle-import") (part "TRANSISTOR-NPN-SOT23"))
    )
    (comp (ref "Q5")
      (value "SS8050W-SOT323")
      (footprint "eagle-import:MOS_SOT323")
      (libsource (lib "eagle-import") (part "TRANS_NPN"))
    )
    (comp (ref "Q6")
      (value "S9013")
      (footprint "eagle-import:SOT23@1")
      (libsource (lib "eagle-import") (part "TRANSISTOR-NPN-SOT23"))
    )
    (comp (ref "Q7")
      (value "BSS138")
      (footprint "eagle-import:SOT23")
      (libsource (lib "eagle-import") (part "MOSFET-N'SOT23'"))
    )
    (comp (ref "Q103")
      (value "S9013")
      (footprint "eagle-import:SOT23@1")
      (libsource (lib "eagle-import") (part "TRANSISTOR-NPN-SOT23"))
    )
    (comp (ref "Q104")
      (value "S9013")
      (footprint "eagle-import:SOT23@1")
      (libsource (lib "eagle-import") (part "TRANSISTOR-NPN-SOT23"))
    )
    (comp (ref "Q115")
      (value "S9013")
      (footprint "eagle-import:SOT23@1")
      (libsource (lib "eagle-import") (part "TRANSISTOR-NPN-SOT23"))
    )
    (comp (ref "Q405")
      (value "2N7002")
      (footprint "eagle-import:SOT23")
      (libsource (lib "eagle-import") (part "MOSFET-N'SOT23'"))
    )
    (comp (ref "R1")
      (value "10K")
      (footprint "eagle-import:R0603")
      (libsource (lib "eagle-import") (part "RESR0603"))
    )
    (comp (ref "R2")
      (value "1K")
      (footprint "eagle-import:R0603")
      (libsource (lib "eagle-import") (part "RESR0603"))
    )
    (comp (ref "R3")
      (value "4.7K 1%")
      (footprint "eagle-import:R0603")
      (libsource (lib "eagle-import") (part "RESR0603"))
    )
    (comp (ref "R4")
      (value "10K")
      (footprint "eagle-import:R0603")
      (libsource (lib "eagle-import") (part "RESR0603"))
    )
    (comp (ref "R5")
      (value "10k")
      (footprint "eagle-import:R0603")
      (libsource (lib "eagle-import") (part "RESR0603"))
    )
    (comp (ref "R6")
      (value "1K")
      (footprint "eagle-import:R0603")
      (libsource (lib "eagle-import") (part "RESR0603"))
    )
    (comp (ref "R7")
      (value "470R")
      (footprint "eagle-import:R0603")
      (libsource (lib "eagle-import") (part "RESR0603"))
    )
    (comp (ref "R8")
      (value "1k")
      (footprint "eagle-import:R0603")
      (libsource (lib "eagle-import") (part "RESR0603"))
    )
    (comp (ref "R9")
      (value "10K")
      (footprint "eagle-import:R0603")
      (libsource (lib "eagle-import") (part "RESR0603"))
    )
    (comp (ref "R10")
      (value "27.4R")
      (footprint "eagle-import:R0603")
      (libsource (lib "eagle-import") (part "RESR0603"))
    )
    (comp (ref "R11")
      (value "27.4R")
      (footprint "eagle-import:R0603")
      (libsource (lib "eagle-import") (part "RESR0603"))
    )
    (comp (ref "R12")
      (value "10K")
      (footprint "eagle-import:R0603")
      (libsource (lib "eagle-import") (part "RESR0603"))
    )
    (comp (ref "R13")
      (value "10K")
      (footprint "eagle-import:R0603")
      (libsource (lib "eagle-import") (part "RESR0603"))
    )
    (comp (ref "R14")
      (value "10K")
      (footprint "eagle-import:R0603")
      (libsource (lib "eagle-import") (part "RESR0603"))
    )
    (comp (ref "R15")
      (value "NC")
      (footprint "eagle-import:R0603")
      (libsource (lib "eagle-import") (part "RESR0603"))
    )
    (comp (ref "R16")
      (value "33R")
      (footprint "eagle-import:R0603")
      (libsource (lib "eagle-import") (part "RESR0603"))
    )
    (comp (ref "R17")
      (value "1K")
      (footprint "eagle-import:R0603")
      (libsource (lib "eagle-import") (part "RESR0603"))
    )
    (comp (ref "R18")
      (value "4.7K")
      (footprint "eagle-import:R0603")
      (libsource (lib "eagle-import") (part "RESR0603"))
    )
    (comp (ref "R19")
      (value "4.7K")
      (footprint "eagle-import:R0603")
      (libsource (lib "eagle-import") (part "RESR0603"))
    )
    (comp (ref "R20")
      (value "100R")
      (footprint "eagle-import:R0603")
      (libsource (lib "eagle-import") (part "RESR0603"))
    )
    (comp (ref "R21")
      (value "10K")
      (footprint "eagle-import:R0603")
      (libsource (lib "eagle-import") (part "RESR0603"))
    )
    (comp (ref "R22")
      (value "1K")
      (footprint "eagle-import:R0603")
      (libsource (lib "eagle-import") (part "RESR0603"))
    )
    (comp (ref "R23")
      (value "470R")
      (footprint "eagle-import:R0603")
      (libsource (lib "eagle-import") (part "RESR0603"))
    )
    (comp (ref "R24")
      (value "4.7K")
      (footprint "eagle-import:R0603")
      (libsource (lib "eagle-import") (part "RESR0603"))
    )
    (comp (ref "R25")
      (value "0R")
      (footprint "eagle-import:R0603")
      (libsource (lib "eagle-import") (part "RESR0603"))
    )
    (comp (ref "R26")
      (value "0R")
      (footprint "eagle-import:R0603")
      (libsource (lib "eagle-import") (part "RESR0603"))
    )
    (comp (ref "R27")
      (value "0R")
      (footprint "eagle-import:R0603")
      (libsource (lib "eagle-import") (part "RESR0603"))
    )
    (comp (ref "R28")
      (value "0R")
      (footprint "eagle-import:R0603")
      (libsource (lib "eagle-import") (part "RESR0603"))
    )
    (comp (ref "R29")
      (value "0R")
      (footprint "eagle-import:R0603")
      (libsource (lib "eagle-import") (part "RESR0603"))
    )
    (comp (ref "R30")
      (value "95.3K")
      (footprint "eagle-import:R0603")
      (libsource (lib "eagle-import") (part "RESR0603"))
    )
    (comp (ref "R32")
      (value "13K")
      (footprint "eagle-import:R0603")
      (libsource (lib "eagle-import") (part "RESR0603"))
    )
    (comp (ref "R34")
      (value "NC")
      (footprint "eagle-import:R0603")
      (libsource (lib "eagle-import") (part "RESR0603"))
    )
    (comp (ref "R35")
      (value "5.1R")
      (footprint "eagle-import:R0603")
      (libsource (lib "eagle-import") (part "RESR0603"))
    )
    (comp (ref "R36")
      (value "4.7K")
      (footprint "eagle-import:R0603")
      (libsource (lib "eagle-import") (part "RESR0603"))
    )
    (comp (ref "R40")
      (value "10R")
      (footprint "eagle-import:R0603")
      (libsource (lib "eagle-import") (part "RESR0603"))
    )
    (comp (ref "R41")
      (value "1K")
      (footprint "eagle-import:R0603")
      (libsource (lib "eagle-import") (part "RESR0603"))
    )
    (comp (ref "R42")
      (value "47K")
      (footprint "eagle-import:R0603")
      (libsource (lib "eagle-import") (part "RESR0603"))
    )
    (comp (ref "R43")
      (value "4.7k")
      (footprint "eagle-import:R0603")
      (libsource (lib "eagle-import") (part "RESR0603"))
    )
    (comp (ref "R44")
      (value "4.7k")
      (footprint "eagle-import:R0603")
      (libsource (lib "eagle-import") (part "RESR0603"))
    )
    (comp (ref "R45")
      (value "4.7k")
      (footprint "eagle-import:R0603")
      (libsource (lib "eagle-import") (part "RESR0603"))
    )
    (comp (ref "R46")
      (value "4.7k")
      (footprint "eagle-import:R0603")
      (libsource (lib "eagle-import") (part "RESR0603"))
    )
    (comp (ref "R47")
      (value "10k")
      (footprint "eagle-import:R0603")
      (libsource (lib "eagle-import") (part "RESR0603"))
    )
    (comp (ref "R54")
      (value "0R")
      (footprint "eagle-import:R0603")
      (libsource (lib "eagle-import") (part "RESR0603"))
    )
    (comp (ref "R56")
      (value "51K")
      (footprint "eagle-import:R0603")
      (libsource (lib "eagle-import") (part "RESR0603"))
    )
    (comp (ref "R57")
      (value "510K")
      (footprint "eagle-import:R0603")
      (libsource (lib "eagle-import") (part "RESR0603"))
    )
    (comp (ref "R58")
      (value "10K")
      (footprint "eagle-import:R0603")
      (libsource (lib "eagle-import") (part "RESR0603"))
    )
    (comp (ref "R59")
      (value "1K")
      (footprint "eagle-import:R0603")
      (libsource (lib "eagle-import") (part "RESR0603"))
    )
    (comp (ref "R61")
      (value "1K")
      (footprint "eagle-import:R0603")
      (libsource (lib "eagle-import") (part "RESR0603"))
    )
    (comp (ref "R62")
      (value "10K")
      (footprint "eagle-import:3P-SMD-SQUA-3.6X3.3")
      (libsource (lib "eagle-import") (part "R-POTENTIOMETER-SMD"))
    )
    (comp (ref "R63")
      (value "10K")
      (footprint "eagle-import:R0603")
      (libsource (lib "eagle-import") (part "RESR0603"))
    )
    (comp (ref "R76")
      (value "30.9K 1%")
      (footprint "eagle-import:R0603")
      (libsource (lib "eagle-import") (part "RESR0603"))
    )
    (comp (ref "R82")
      (value "0R")
      (footprint "eagle-import:R0603")
      (libsource (lib "eagle-import") (part "R0603"))
    )
    (comp (ref "R83")
      (value "0R")
      (footprint "eagle-import:R0603")
      (libsource (lib "eagle-import") (part "R0603"))
    )
    (comp (ref "R84")
      (value "4.7K")
      (footprint "eagle-import:R0603")
      (libsource (lib "eagle-import") (part "R0603"))
    )
    (comp (ref "R85")
      (value "4.7K")
      (footprint "eagle-import:R0603")
      (libsource (lib "eagle-import") (part "R0603"))
    )
    (comp (ref "R107")
      (value "10K")
      (footprint "eagle-import:R0603")
      (libsource (lib "eagle-import") (part "RESR0603"))
    )
    (comp (ref "R115")
      (value "10K")
      (footprint "eagle-import:R0603")
      (libsource (lib "eagle-import") (part "RESR0603"))
    )
    (comp (ref "R116")
      (value "10K")
      (footprint "eagle-import:R0603")
      (libsource (lib "eagle-import") (part "RESR0603"))
    )
    (comp (ref "R117")
      (value "14k")
      (footprint "eagle-import:R0603")
      (libsource (lib "eagle-import") (part "RESR0603"))
    )
    (comp (ref "R118")
      (value "NC")
      (footprint "eagle-import:R0603")
      (libsource (lib "eagle-import") (part "RESR0603"))
    )
    (comp (ref "R190")
      (value "3.3k")
      (footprint "eagle-import:R0603")
      (libsource (lib "eagle-import") (part "RESR0603"))
    )
    (comp (ref "R191")
      (value "10K")
      (footprint "eagle-import:R0603")
      (libsource (lib "eagle-import") (part "RESR0603"))
    )
    (comp (ref "R273")
      (value "10K")
      (footprint "eagle-import:R0603")
      (libsource (lib "eagle-import") (part "RESR0603"))
    )
    (comp (ref "R274")
      (value "1K")
      (footprint "eagle-import:R0603")
      (libsource (lib "eagle-import") (part "RESR0603"))
    )
    (comp (ref "R276")
      (value "22R")
      (footprint "eagle-import:R0603")
      (libsource (lib "eagle-import") (part "RESR0603"))
    )
    (comp (ref "R280")
      (value "10K")
      (footprint "eagle-import:R0603")
      (libsource (lib "eagle-import") (part "RESR0603"))
    )
    (comp (ref "R282")
      (value "2K")
      (footprint "eagle-import:R0603")
      (libsource (lib "eagle-import") (part "RESR0603"))
    )
    (comp (ref "R283")
      (value "22R")
      (footprint "eagle-import:R0603")
      (libsource (lib "eagle-import") (part "RESR0603"))
    )
    (comp (ref "R284")
      (value "2K")
      (footprint "eagle-import:R0603")
      (libsource (lib "eagle-import") (part "RESR0603"))
    )
    (comp (ref "R286")
      (value "10K")
      (footprint "eagle-import:R0603")
      (libsource (lib "eagle-import") (part "RESR0603"))
    )
    (comp (ref "R287")
      (value "1K")
      (footprint "eagle-import:R0603")
      (libsource (lib "eagle-import") (part "RESR0603"))
    )
    (comp (ref "R288")
      (value "10K")
      (footprint "eagle-import:R0603")
      (libsource (lib "eagle-import") (part "RESR0603"))
    )
    (comp (ref "R299")
      (value "2K")
      (footprint "eagle-import:R0603")
      (libsource (lib "eagle-import") (part "RESR0603"))
    )
    (comp (ref "R301")
      (value "10K")
      (footprint "eagle-import:R0603")
      (libsource (lib "eagle-import") (part "RESR0603"))
    )
    (comp (ref "R302")
      (value "10K")
      (footprint "eagle-import:R0603")
      (libsource (lib "eagle-import") (part "RESR0603"))
    )
    (comp (ref "R303")
      (value "22R")
      (footprint "eagle-import:R0603")
      (libsource (lib "eagle-import") (part "RESR0603"))
    )
    (comp (ref "R329")
      (value "NC")
      (footprint "eagle-import:R0603")
      (libsource (lib "eagle-import") (part "RESR0603"))
    )
    (comp (ref "R411")
      (value "30K/1%")
      (footprint "eagle-import:R0603")
      (libsource (lib "eagle-import") (part "RESR0603"))
    )
    (comp (ref "R412")
      (value "18K/1%")
      (footprint "eagle-import:R0603")
      (libsource (lib "eagle-import") (part "RESR0603"))
    )
    (comp (ref "R422")
      (value "4.7k")
      (footprint "eagle-import:R0603")
      (libsource (lib "eagle-import") (part "RESR0603"))
    )
    (comp (ref "R423")
      (value "4.7K")
      (footprint "eagle-import:R0603")
      (libsource (lib "eagle-import") (part "RESR0603"))
    )
    (comp (ref "R622")
      (value "200K")
      (footprint "eagle-import:R0603")
      (libsource (lib "eagle-import") (part "RESR0603"))
    )
    (comp (ref "R639")
      (value "1K")
      (footprint "eagle-import:R0603")
      (libsource (lib "eagle-import") (part "RESR0603"))
    )
    (comp (ref "R652")
      (value "2.7K")
      (footprint "eagle-import:R0603")
      (libsource (lib "eagle-import") (part "RESR0603"))
    )
    (comp (ref "R653")
      (value "3.74K")
      (footprint "eagle-import:R0603")
      (libsource (lib "eagle-import") (part "RESR0603"))
    )
    (comp (ref "R654")
      (value "5.6K")
      (footprint "eagle-import:R0603")
      (libsource (lib "eagle-import") (part "RESR0603"))
    )
    (comp (ref "R655")
      (value "8.2K")
      (footprint "eagle-import:R0603")
      (libsource (lib "eagle-import") (part "RESR0603"))
    )
    (comp (ref "RELAY1")
      (value "RELAY-SRD")
      (footprint "eagle-import:REY5-6-19.1X15.5X15.3MM")
      (libsource (lib "eagle-import") (part "RELAY-SRD"))
    )
    (comp (ref "RESET")
      (value "TS3425BA")
      (footprint "eagle-import:SMD_KEY4.2_3._.2.5")
      (libsource (lib "eagle-import") (part "KEY"))
    )
    (comp (ref "U1")
      (value "RP2350A")
      (footprint "eagle-import:QFN-60_7X7MM")
      (libsource (lib "eagle-import") (part "RP2350A"))
    )
    (comp (ref "U2")
      (value "APS6404L")
      (footprint "eagle-import:SOP-8L")
      (libsource (lib "eagle-import") (part "APS6404L"))
    )
    (comp (ref "U3")
      (value "W25Q64JVXGIQ")
      (footprint "eagle-import:W25QXX-XSON-8-EP(4X4)")
      (libsource (lib "eagle-import") (part "W25QXX"))
    )
    (comp (ref "U5")
      (value "DHT20")
      (footprint "eagle-import:CROWTAIL-DHT20-V1.0-20211013_DHT20")
      (libsource (lib "eagle-import") (part "CROWTAIL-DHT20-V1.0-20211013_DHT20"))
    )
    (comp (ref "U6")
      (value "HAL248")
      (footprint "eagle-import:SOT-23W")
      (libsource (lib "eagle-import") (part "A1101"))
    )
    (comp (ref "U7")
      (value "BH1750")
      (footprint "eagle-import:BH1750-WSOF-6")
      (libsource (lib "eagle-import") (part "BH1750"))
    )
    (comp (ref "U8")
      (value "MT3608")
      (footprint "eagle-import:DBV_R-PDSO-G6")
      (libsource (lib "eagle-import") (part "MT3608"))
    )
    (comp (ref "U10")
      (value "SN74LVC1G125")
      (footprint "eagle-import:SOT23-5")
      (libsource (lib "eagle-import") (part "SN74LVC1G125"))
    )
    (comp (ref "U11")
      (value "LM393")
      (footprint "eagle-import:SOP8@1")
      (libsource (lib "eagle-import") (part "IC_LM393_SOP8"))
    )
    (comp (ref "U12")
      (value "LSM6DS3TR-C")
      (footprint "eagle-import:LGA-14L")
      (libsource (lib "eagle-import") (part "LSM6DS3"))
    )
    (comp (ref "U30")
      (value "MT2492")
      (footprint "eagle-import:MT2492-SOT23-6")
      (libsource (lib "eagle-import") (part "MT2492"))
    )
    (comp (ref "U34")
      (value "LPW5206AB5F")
      (footprint "eagle-import:IC_SOT23-5")
      (libsource (lib "eagle-import") (part "LPW5206B5F_SOT23-5"))
    )
    (comp (ref "U41")
      (value "PW1503")
      (footprint "eagle-import:SOT23-5")
      (libsource (lib "eagle-import") (part "PW1503"))
    )
    (comp (ref "U123")
      (value "TTP223")
      (footprint "eagle-import:SOT23-6L")
      (libsource (lib "eagle-import") (part "TTP223"))
    )
    (comp (ref "U309")
      (value "IR-3PSIP3")
      (footprint "eagle-import:VS1838B-SIP3")
      (libsource (lib "eagle-import") (part "IR-3PSIP3"))
    )
    (comp (ref "U401")
      (value "TD1509")
      (footprint "eagle-import:TD1509")
      (libsource (lib "eagle-import") (part "TD1509"))
    )
    (comp (ref "X1")
      (value "X322512MSB4SI")
      (footprint "eagle-import:A_XBJ_SMD3225")
      (libsource (lib "eagle-import") (part "A_XBJ_XTAL"))
    )
  )
  (nets
    (net (code "1") (name "+1V1") (class "Default")
      (node (ref "C15") (pin "1") (pinfunction "1_1") (pintype "passive"))
      (node (ref "C24") (pin "1") (pinfunction "1_1") (pintype "passive"))
      (node (ref "C26") (pin "2") (pinfunction "2_2") (pintype "passive"))
      (node (ref "C4") (pin "1") (pinfunction "1_1") (pintype "passive"))
      (node (ref "L1") (pin "P$1") (pinfunction "1_P$1") (pintype "passive"))
      (node (ref "U1") (pin "P$23") (pinfunction "DVDD1_P$23") (pintype "power_in"))
      (node (ref "U1") (pin "P$39") (pinfunction "DVDD0_P$39") (pintype "power_in"))
      (node (ref "U1") (pin "P$50") (pinfunction "VREG_FB_P$50") (pintype "bidirectional"))
      (node (ref "U1") (pin "P$6") (pinfunction "DVDD2_P$6") (pintype "power_in"))
    )
    (net (code "2") (name "/COM") (class "Default")
      (node (ref "J123") (pin "2") (pinfunction "P$2_2") (pintype "bidirectional"))
      (node (ref "RELAY1") (pin "2") (pinfunction "2_2") (pintype "bidirectional"))
    )
    (net (code "3") (name "/DC_OUT1") (class "Default")
      (node (ref "D007") (pin "C") (pinfunction "C_C") (pintype "passive"))
      (node (ref "L401") (pin "1") (pinfunction "1_1") (pintype "bidirectional"))
      (node (ref "U401") (pin "P$2") (pinfunction "2_VOUT_P$2") (pintype "bidirectional"))
    )
    (net (code "4") (name "/FB1") (class "Default")
      (node (ref "C412") (pin "1") (pinfunction "1_1") (pintype "passive"))
      (node (ref "R411") (pin "1") (pinfunction "1_1") (pintype "passive"))
      (node (ref "R412") (pin "2") (pinfunction "2_2") (pintype "passive"))
      (node (ref "U401") (pin "P$3") (pinfunction "3_FB_P$3") (pintype "bidirectional"))
    )
    (net (code "5") (name "/IO1_HALL") (class "Default")
      (node (ref "C34") (pin "2") (pinfunction "2_2") (pintype "passive"))
      (node (ref "Q7") (pin "3") (pinfunction "D_3") (pintype "passive"))
      (node (ref "R34") (pin "2") (pinfunction "2_2") (pintype "passive"))
      (node (ref "R63") (pin "1") (pinfunction "1_1") (pintype "passive"))
      (node (ref "U6") (pin "2") (pinfunction "VOUT_2") (pintype "output"))
    )
    (net (code "6") (name "/IO_RGB_OUT") (class "Default")
      (node (ref "D183") (pin "4") (pinfunction "4_DIN_4") (pintype "bidirectional"))
      (node (ref "U10") (pin "4") (pinfunction "Y_4") (pintype "bidirectional"))
    )
    (net (code "7") (name "/NC") (class "Default")
      (node (ref "J123") (pin "1") (pinfunction "P$1_1") (pintype "bidirectional"))
      (node (ref "RELAY1") (pin "4") (pinfunction "4_4") (pintype "bidirectional"))
    )
    (net (code "8") (name "/NO") (class "Default")
      (node (ref "J123") (pin "3") (pinfunction "P$3_3") (pintype "bidirectional"))
      (node (ref "RELAY1") (pin "5") (pinfunction "5_5") (pintype "bidirectional"))
    )
    (net (code "9") (name "/V+") (class "Default")
      (node (ref "R276") (pin "2") (pinfunction "2_2") (pintype "passive"))
      (node (ref "RELAY1") (pin "1") (pinfunction "1_1") (pintype "bidirectional"))
    )
    (net (code "10") (name "/V-") (class "Default")
      (node (ref "D002") (pin "+") (pinfunction "+_+") (pintype "passive"))
      (node (ref "LED1") (pin "-") (pinfunction "-_-") (pintype "passive"))
      (node (ref "Q115") (pin "3") (pinfunction "C_3") (pintype "passive"))
      (node (ref "RELAY1") (pin "3") (pinfunction "3_3") (pintype "bidirectional"))
    )
    (net (code "11") (name "/VCC_RELAY") (class "Default")
      (node (ref "C36") (pin "2") (pinfunction "2_2") (pintype "passive"))
      (node (ref "D002") (pin "-") (pinfunction "-_-") (pintype "passive"))
      (node (ref "L11") (pin "2") (pinfunction "2_2") (pintype "bidirectional"))
      (node (ref "R24") (pin "2") (pinfunction "2_2") (pintype "passive"))
      (node (ref "R276") (pin "1") (pinfunction "1_1") (pintype "passive"))
    )
    (net (code "12") (name "BOOT") (class "Default")
      (node (ref "BOOT") (pin "P$1") (pinfunction "1_P$1") (pintype "bidirectional"))
      (node (ref "R2") (pin "2") (pinfunction "2_2") (pintype "passive"))
    )
    (net (code "13") (name "CORE_RESET") (class "Default")
      (node (ref "C14") (pin "2") (pinfunction "2_2") (pintype "passive"))
      (node (ref "D001") (pin "-") (pinfunction "-_-") (pintype "passive"))
      (node (ref "R5") (pin "1") (pinfunction "1_1") (pintype "passive"))
      (node (ref "RESET") (pin "P$2") (pinfunction "2_P$2") (pintype "bidirectional"))
      (node (ref "U1") (pin "P$26") (pinfunction "RUN_P$26") (pintype "bidirectional"))
    )
    (net (code "14") (name "GND") (class "Default")
      (node (ref "BOOT") (pin "P$4") (pinfunction "4_P$4") (pintype "bidirectional"))
      (node (ref "C1") (pin "1") (pinfunction "1_1") (pintype "passive"))
      (node (ref "C10") (pin "2") (pinfunction "2_2") (pintype "passive"))
      (node (ref "C11") (pin "2") (pinfunction "2_2") (pintype "passive"))
      (node (ref "C12") (pin "2") (pinfunction "2_2") (pintype "passive"))
      (node (ref "C13") (pin "2") (pinfunction "2_2") (pintype "passive"))
      (node (ref "C14") (pin "1") (pinfunction "1_1") (pintype "passive"))
      (node (ref "C15") (pin "2") (pinfunction "2_2") (pintype "passive"))
      (node (ref "C16") (pin "2") (pinfunction "2_2") (pintype "passive"))
      (node (ref "C17") (pin "2") (pinfunction "2_2") (pintype "passive"))
      (node (ref "C18") (pin "1") (pinfunction "1_1") (pintype "passive"))
      (node (ref "C183") (pin "2") (pinfunction "2_2") (pintype "passive"))
      (node (ref "C19") (pin "2") (pinfunction "2_2") (pintype "passive"))
      (node (ref "C2") (pin "2") (pinfunction "2_2") (pintype "passive"))
      (node (ref "C20") (pin "2") (pinfunction "2_2") (pintype "passive"))
      (node (ref "C21") (pin "2") (pinfunction "2_2") (pintype "passive"))
      (node (ref "C212") (pin "1") (pinfunction "1_1") (pintype "passive"))
      (node (ref "C213") (pin "1") (pinfunction "1_1") (pintype "passive"))
      (node (ref "C214") (pin "1") (pinfunction "1_1") (pintype "passive"))
      (node (ref "C22") (pin "2") (pinfunction "2_2") (pintype "passive"))
      (node (ref "C23") (pin "2") (pinfunction "2_2") (pintype "passive"))
      (node (ref "C24") (pin "2") (pinfunction "2_2") (pintype "passive"))
      (node (ref "C25") (pin "1") (pinfunction "1_1") (pintype "passive"))
      (node (ref "C26") (pin "1") (pinfunction "1_1") (pintype "passive"))
      (node (ref "C27") (pin "2") (pinfunction "2_2") (pintype "passive"))
      (node (ref "C28") (pin "2") (pinfunction "2_2") (pintype "passive"))
      (node (ref "C29") (pin "2") (pinfunction "2_2") (pintype "passive"))
      (node (ref "C3") (pin "1") (pinfunction "1_1") (pintype "passive"))
      (node (ref "C30") (pin "2") (pinfunction "2_2") (pintype "passive"))
      (node (ref "C31") (pin "-") (pinfunction "-_-") (pintype "passive"))
      (node (ref "C32") (pin "1") (pinfunction "1_1") (pintype "passive"))
      (node (ref "C33") (pin "1") (pinfunction "1_1") (pintype "passive"))
      (node (ref "C34") (pin "1") (pinfunction "1_1") (pintype "passive"))
      (node (ref "C35") (pin "1") (pinfunction "1_1") (pintype "passive"))
      (node (ref "C36") (pin "1") (pinfunction "1_1") (pintype "passive"))
      (node (ref "C37") (pin "1") (pinfunction "1_1") (pintype "passive"))
      (node (ref "C38") (pin "1") (pinfunction "1_1") (pintype "passive"))
      (node (ref "C39") (pin "1") (pinfunction "1_1") (pintype "passive"))
      (node (ref "C4") (pin "2") (pinfunction "2_2") (pintype "passive"))
      (node (ref "C40") (pin "1") (pinfunction "1_1") (pintype "passive"))
      (node (ref "C409") (pin "1") (pinfunction "1_1") (pintype "passive"))
      (node (ref "C41") (pin "1") (pinfunction "1_1") (pintype "passive"))
      (node (ref "C411") (pin "1") (pinfunction "1_1") (pintype "passive"))
      (node (ref "C413") (pin "2") (pinfunction "2_2") (pintype "passive"))
      (node (ref "C414") (pin "2") (pinfunction "2_2") (pintype "passive"))
      (node (ref "C42") (pin "1") (pinfunction "1_1") (pintype "passive"))
      (node (ref "C43") (pin "1") (pinfunction "1_1") (pintype "passive"))
      (node (ref "C44") (pin "2") (pinfunction "2_2") (pintype "passive"))
      (node (ref "C45") (pin "1") (pinfunction "1_1") (pintype "passive"))
      (node (ref "C46") (pin "2") (pinfunction "2_2") (pintype "passive"))
      (node (ref "C47") (pin "1") (pinfunction "1_1") (pintype "passive"))
      (node (ref "C48") (pin "1") (pinfunction "1_1") (pintype "passive"))
      (node (ref "C49") (pin "1") (pinfunction "1_1") (pintype "passive"))
      (node (ref "C5") (pin "1") (pinfunction "1_1") (pintype "passive"))
      (node (ref "C50") (pin "1") (pinfunction "1_1") (pintype "passive"))
      (node (ref "C51") (pin "2") (pinfunction "2_2") (pintype "passive"))
      (node (ref "C52") (pin "1") (pinfunction "1_1") (pintype "passive"))
      (node (ref "C55") (pin "1") (pinfunction "1_1") (pintype "passive"))
      (node (ref "C56") (pin "1") (pinfunction "1_1") (pintype "passive"))
      (node (ref "C57") (pin "2") (pinfunction "2_2") (pintype "passive"))
      (node (ref "C58") (pin "1") (pinfunction "1_1") (pintype "passive"))
      (node (ref "C59") (pin "1") (pinfunction "1_1") (pintype "passive"))
      (node (ref "C6") (pin "1") (pinfunction "1_1") (pintype "passive"))
      (node (ref "C60") (pin "1") (pinfunction "1_1") (pintype "passive"))
      (node (ref "C64") (pin "1") (pinfunction "1_1") (pintype "passive"))
      (node (ref "C66") (pin "2") (pinfunction "2_2") (pintype "passive"))
      (node (ref "C67") (pin "1") (pinfunction "1_1") (pintype "passive"))
      (node (ref "C68") (pin "1") (pinfunction "1_1") (pintype "passive"))
      (node (ref "C7") (pin "1") (pinfunction "1_1") (pintype "passive"))
      (node (ref "C8") (pin "2") (pinfunction "2_2") (pintype "passive"))
      (node (ref "C90") (pin "2") (pinfunction "2_2") (pintype "passive"))
      (node (ref "D007") (pin "A") (pinfunction "A_A") (pintype "passive"))
      (node (ref "D012") (pin "3") (pinfunction "3_GND_3") (pintype "bidirectional"))
      (node (ref "D019") (pin "3") (pinfunction "3_GND_3") (pintype "bidirectional"))
      (node (ref "D021") (pin "3") (pinfunction "3_GND_3") (pintype "bidirectional"))
      (node (ref "D022") (pin "3") (pinfunction "3_GND_3") (pintype "bidirectional"))
      (node (ref "D023") (pin "3") (pinfunction "3_GND_3") (pintype "bidirectional"))
      (node (ref "D024") (pin "3") (pinfunction "3_GND_3") (pintype "bidirectional"))
      (node (ref "D025") (pin "3") (pinfunction "3_GND_3") (pintype "bidirectional"))
      (node (ref "D026") (pin "3") (pinfunction "3_GND_3") (pintype "bidirectional"))
      (node (ref "D027") (pin "3") (pinfunction "3_GND_3") (pintype "bidirectional"))
      (node (ref "D028") (pin "3") (pinfunction "3_GND_3") (pintype "bidirectional"))
      (node (ref "D029") (pin "3") (pinfunction "3_GND_3") (pintype "bidirectional"))
      (node (ref "D030") (pin "3") (pinfunction "3_GND_3") (pintype "bidirectional"))
      (node (ref "D031") (pin "3") (pinfunction "3_GND_3") (pintype "bidirectional"))
      (node (ref "D032") (pin "3") (pinfunction "3_GND_3") (pintype "bidirectional"))
      (node (ref "D033") (pin "3") (pinfunction "3_GND_3") (pintype "bidirectional"))
      (node (ref "D183") (pin "3") (pinfunction "3_GND_3") (pintype "bidirectional"))
      (node (ref "D184") (pin "3") (pinfunction "3_GND_3") (pintype "bidirectional"))
      (node (ref "D185") (pin "3") (pinfunction "3_GND_3") (pintype "bidirectional"))
      (node (ref "D186") (pin "3") (pinfunction "3_GND_3") (pintype "bidirectional"))
      (node (ref "D187") (pin "3") (pinfunction "3_GND_3") (pintype "bidirectional"))
      (node (ref "FPC1") (pin "P$1") (pinfunction "GND_P$1") (pintype "bidirectional"))
      (node (ref "FPC1") (pin "P$16") (pinfunction "GND_P$16") (pintype "bidirectional"))
      (node (ref "FPC1") (pin "P$17") (pinfunction "G2_P$17") (pintype "bidirectional"))
      (node (ref "FPC1") (pin "P$18") (pinfunction "G1_P$18") (pintype "bidirectional"))
      (node (ref "J1") (pin "4") (pinfunction "4_4") (pintype "bidirectional"))
      (node (ref "J1") (pin "SS1") (pinfunction "SS1_SS1") (pintype "bidirectional"))
      (node (ref "J1") (pin "SS2") (pinfunction "SS2_SS2") (pintype "bidirectional"))
      (node (ref "J14") (pin "P$1") (pinfunction "1_GND_P$1") (pintype "bidirectional"))
      (node (ref "J15") (pin "3") (pinfunction "S_3") (pintype "bidirectional"))
      (node (ref "J3") (pin "2") (pinfunction "-_2") (pintype "bidirectional"))
      (node (ref "J7") (pin "1") (pinfunction "1_1") (pintype "bidirectional"))
      (node (ref "J8") (pin "4") (pinfunction "4_4") (pintype "bidirectional"))
      (node (ref "J8") (pin "5") (pinfunction "SS1_5") (pintype "bidirectional"))
      (node (ref "J8") (pin "6") (pinfunction "SS2_6") (pintype "bidirectional"))
      (node (ref "K1") (pin "P$1") (pinfunction "P$1_P$1") (pintype "bidirectional"))
      (node (ref "K2") (pin "P$1") (pinfunction "P$1_P$1") (pintype "bidirectional"))
      (node (ref "K3") (pin "P$1") (pinfunction "P$1_P$1") (pintype "bidirectional"))
      (node (ref "K4") (pin "P$1") (pinfunction "P$1_P$1") (pintype "bidirectional"))
      (node (ref "P11") (pin "P$1") (pinfunction "P$1_P$1") (pintype "bidirectional"))
      (node (ref "P2") (pin "1") (pinfunction "1_1") (pintype "passive"))
      (node (ref "P24") (pin "P$1") (pinfunction "P$1_P$1") (pintype "bidirectional"))
      (node (ref "P4") (pin "P$1") (pinfunction "P$1_P$1") (pintype "bidirectional"))
      (node (ref "P9") (pin "P$1") (pinfunction "P$1_P$1") (pintype "bidirectional"))
      (node (ref "Q1") (pin "2") (pinfunction "E_2") (pintype "passive"))
      (node (ref "Q103") (pin "2") (pinfunction "E_2") (pintype "passive"))
      (node (ref "Q104") (pin "2") (pinfunction "E_2") (pintype "passive"))
      (node (ref "Q115") (pin "2") (pinfunction "E_2") (pintype "passive"))
      (node (ref "Q2") (pin "2") (pinfunction "E_2") (pintype "passive"))
      (node (ref "Q3") (pin "2") (pinfunction "E_2") (pintype "passive"))
      (node (ref "Q5") (pin "2") (pinfunction "E_2") (pintype "passive"))
      (node (ref "Q6") (pin "2") (pinfunction "E_2") (pintype "passive"))
      (node (ref "R115") (pin "2") (pinfunction "2_2") (pintype "passive"))
      (node (ref "R117") (pin "2") (pinfunction "2_2") (pintype "passive"))
      (node (ref "R13") (pin "1") (pinfunction "1_1") (pintype "passive"))
      (node (ref "R15") (pin "1") (pinfunction "1_1") (pintype "passive"))
      (node (ref "R190") (pin "2") (pinfunction "2_2") (pintype "passive"))
      (node (ref "R21") (pin "1") (pinfunction "1_1") (pintype "passive"))
      (node (ref "R273") (pin "1") (pinfunction "1_1") (pintype "passive"))
      (node (ref "R280") (pin "1") (pinfunction "1_1") (pintype "passive"))
      (node (ref "R286") (pin "2") (pinfunction "2_2") (pintype "passive"))
      (node (ref "R288") (pin "2") (pinfunction "2_2") (pintype "passive"))
      (node (ref "R3") (pin "1") (pinfunction "1_1") (pintype "passive"))
      (node (ref "R302") (pin "1") (pinfunction "1_1") (pintype "passive"))
      (node (ref "R32") (pin "2") (pinfunction "2_2") (pintype "passive"))
      (node (ref "R35") (pin "1") (pinfunction "1_1") (pintype "passive"))
      (node (ref "R36") (pin "2") (pinfunction "2_2") (pintype "passive"))
      (node (ref "R4") (pin "1") (pinfunction "1_1") (pintype "passive"))
      (node (ref "R412") (pin "1") (pinfunction "1_1") (pintype "passive"))
      (node (ref "R42") (pin "2") (pinfunction "2_2") (pintype "passive"))
      (node (ref "R56") (pin "2") (pinfunction "2_2") (pintype "passive"))
      (node (ref "R62") (pin "1") (pinfunction "1_1") (pintype "passive"))
      (node (ref "R622") (pin "2") (pinfunction "2_2") (pintype "passive"))
      (node (ref "R82") (pin "1") (pinfunction "1_1") (pintype "passive"))
      (node (ref "R83") (pin "1") (pinfunction "1_1") (pintype "passive"))
      (node (ref "RESET") (pin "P$3") (pinfunction "3_P$3") (pintype "bidirectional"))
      (node (ref "U1") (pin "P$47") (pinfunction "VREG_PGND_P$47") (pintype "bidirectional"))
      (node (ref "U1") (pin "P$61") (pinfunction "GND_P$61") (pintype "bidirectional"))
      (node (ref "U10") (pin "1") (pinfunction "OE_1") (pintype "bidirectional"))
      (node (ref "U10") (pin "3") (pinfunction "GND_3") (pintype "bidirectional"))
      (node (ref "U11") (pin "4") (pinfunction "4_GND_4") (pintype "bidirectional"))
      (node (ref "U12") (pin "6") (pinfunction "GND_6") (pintype "power_in"))
      (node (ref "U12") (pin "7") (pinfunction "GND_7") (pintype "power_in"))
      (node (ref "U123") (pin "2") (pinfunction "GND_2") (pintype "bidirectional"))
      (node (ref "U2") (pin "P$4") (pinfunction "VSS_P$4") (pintype "bidirectional"))
      (node (ref "U3") (pin "4") (pinfunction "GND_4") (pintype "bidirectional"))
      (node (ref "U3") (pin "EP") (pinfunction "GND_EP") (pintype "bidirectional"))
      (node (ref "U30") (pin "2") (pinfunction "GND_2") (pintype "bidirectional"))
      (node (ref "U309") (pin "2") (pinfunction "P$2_2") (pintype "bidirectional"))
      (node (ref "U34") (pin "2") (pinfunction "2_GND_2") (pintype "bidirectional"))
      (node (ref "U401") (pin "P$4") (pinfunction "4_EN_P$4") (pintype "bidirectional"))
      (node (ref "U401") (pin "P$5") (pinfunction "5_GND_P$5") (pintype "bidirectional"))
      (node (ref "U401") (pin "P$6") (pinfunction "6_GND_P$6") (pintype "bidirectional"))
      (node (ref "U401") (pin "P$7") (pinfunction "7_GND_P$7") (pintype "bidirectional"))
      (node (ref "U401") (pin "P$8") (pinfunction "8_GND_P$8") (pintype "bidirectional"))
      (node (ref "U41") (pin "2") (pinfunction "GND_2") (pintype "bidirectional"))
      (node (ref "U5") (pin "3") (pinfunction "GND_3") (pintype "bidirectional"))
      (node (ref "U6") (pin "3") (pinfunction "GND_3") (pintype "power_in"))
      (node (ref "U7") (pin "3") (pinfunction "GND\\_3") (pintype "bidirectional"))
      (node (ref "U8") (pin "2") (pinfunction "GND_2") (pintype "bidirectional"))
      (node (ref "X1") (pin "2") (pinfunction "GND_2") (pintype "bidirectional"))
      (node (ref "X1") (pin "4") (pinfunction "GND_4") (pintype "bidirectional"))
    )
    (net (code "15") (name "GP0_LED_BK") (class "Default")
      (node (ref "R41") (pin "2") (pinfunction "2_2") (pintype "passive"))
      (node (ref "U1") (pin "P$2") (pinfunction "GPIO0_P$2") (pintype "bidirectional"))
    )
    (net (code "16") (name "GP1_PSRAM_CS") (class "Default")
      (node (ref "R14") (pin "1") (pinfunction "1_1") (pintype "passive"))
      (node (ref "U1") (pin "P$3") (pinfunction "GPIO1_P$3") (pintype "bidirectional"))
      (node (ref "U2") (pin "P$1") (pinfunction "/CE_P$1") (pintype "bidirectional"))
    )
    (net (code "17") (name "GP2{slash}I2C1_SDA") (class "Default")
      (node (ref "R18") (pin "2") (pinfunction "2_2") (pintype "passive"))
      (node (ref "R26") (pin "2") (pinfunction "2_2") (pintype "passive"))
      (node (ref "U12") (pin "14") (pinfunction "SDA_14") (pintype "bidirectional"))
      (node (ref "U5") (pin "2") (pinfunction "SDA_2") (pintype "bidirectional"))
      (node (ref "U7") (pin "4") (pinfunction "SDA_4") (pintype "bidirectional"))
    )
    (net (code "18") (name "GP3{slash}I2C1_SCL") (class "Default")
      (node (ref "R19") (pin "2") (pinfunction "2_2") (pintype "passive"))
      (node (ref "R27") (pin "2") (pinfunction "2_2") (pintype "passive"))
      (node (ref "U12") (pin "13") (pinfunction "SCL_13") (pintype "bidirectional"))
      (node (ref "U5") (pin "4") (pinfunction "SCL_4") (pintype "bidirectional"))
      (node (ref "U7") (pin "6") (pinfunction "SCL_6") (pintype "bidirectional"))
    )
    (net (code "19") (name "GP4{slash}I2C0_SDA") (class "Default")
      (node (ref "FPC1") (pin "P$4") (pinfunction "YD/CTP_SDA_P$4") (pintype "bidirectional"))
      (node (ref "P16") (pin "P$1") (pinfunction "P$1_P$1") (pintype "bidirectional"))
      (node (ref "R28") (pin "2") (pinfunction "2_2") (pintype "passive"))
      (node (ref "R45") (pin "1") (pinfunction "1_1") (pintype "passive"))
    )
    (net (code "20") (name "GP5{slash}I2C0_SCL") (class "Default")
      (node (ref "FPC1") (pin "P$3") (pinfunction "XR/CTP_SCL_P$3") (pintype "bidirectional"))
      (node (ref "P15") (pin "P$1") (pinfunction "P$1_P$1") (pintype "bidirectional"))
      (node (ref "R29") (pin "2") (pinfunction "2_2") (pintype "passive"))
      (node (ref "R46") (pin "1") (pinfunction "1_1") (pintype "passive"))
    )
    (net (code "21") (name "GP6_SPI0_CLK_TFT") (class "Default")
      (node (ref "FPC1") (pin "P$13") (pinfunction "SCL_P$13") (pintype "bidirectional"))
      (node (ref "P21") (pin "P$1") (pinfunction "P$1_P$1") (pintype "bidirectional"))
      (node (ref "R43") (pin "1") (pinfunction "1_1") (pintype "passive"))
      (node (ref "U1") (pin "P$9") (pinfunction "GPIO6_P$9") (pintype "bidirectional"))
    )
    (net (code "22") (name "GP7_SPI0_MOSI_TFT") (class "Default")
      (node (ref "FPC1") (pin "P$14") (pinfunction "SDI_P$14") (pintype "bidirectional"))
      (node (ref "P22") (pin "P$1") (pinfunction "P$1_P$1") (pintype "bidirectional"))
      (node (ref "R44") (pin "1") (pinfunction "1_1") (pintype "passive"))
      (node (ref "U1") (pin "P$10") (pinfunction "GPIO7_P$10") (pintype "bidirectional"))
    )
    (net (code "23") (name "GP16_RS_TFT") (class "Default")
      (node (ref "FPC1") (pin "P$7") (pinfunction "RS_P$7") (pintype "bidirectional"))
      (node (ref "P19") (pin "P$1") (pinfunction "P$1_P$1") (pintype "bidirectional"))
      (node (ref "U1") (pin "P$27") (pinfunction "GPIO16_P$27") (pintype "bidirectional"))
    )
    (net (code "24") (name "GP17_SPI0_CS_TFT") (class "Default")
      (node (ref "FPC1") (pin "P$12") (pinfunction "CS_P$12") (pintype "bidirectional"))
      (node (ref "P20") (pin "P$1") (pinfunction "P$1_P$1") (pintype "bidirectional"))
      (node (ref "U1") (pin "P$28") (pinfunction "GPIO17_P$28") (pintype "bidirectional"))
    )
    (net (code "25") (name "GP26_A0_GAS") (class "Default")
      (node (ref "J2") (pin "4") (pinfunction "B_4") (pintype "bidirectional"))
      (node (ref "J2") (pin "6") (pinfunction "B_6") (pintype "bidirectional"))
      (node (ref "R36") (pin "1") (pinfunction "1_1") (pintype "passive"))
      (node (ref "U1") (pin "P$40") (pinfunction "GPIO26_ADC0_P$40") (pintype "bidirectional"))
    )
    (net (code "26") (name "GP27_A1_KEY") (class "Default")
      (node (ref "P61") (pin "P$1") (pinfunction "P$1_P$1") (pintype "bidirectional"))
      (node (ref "R639") (pin "2") (pinfunction "2_2") (pintype "passive"))
      (node (ref "R652") (pin "2") (pinfunction "2_2") (pintype "passive"))
      (node (ref "R653") (pin "2") (pinfunction "2_2") (pintype "passive"))
      (node (ref "R654") (pin "2") (pinfunction "2_2") (pintype "passive"))
      (node (ref "R655") (pin "2") (pinfunction "2_2") (pintype "passive"))
      (node (ref "U1") (pin "P$41") (pinfunction "GPIO27_ADC1_P$41") (pintype "bidirectional"))
    )
    (net (code "27") (name "GP28_A2_POT") (class "Default")
      (node (ref "C18") (pin "2") (pinfunction "2_2") (pintype "passive"))
      (node (ref "C40") (pin "2") (pinfunction "2_2") (pintype "passive"))
      (node (ref "P2") (pin "2") (pinfunction "3_2") (pintype "passive"))
      (node (ref "U1") (pin "P$42") (pinfunction "GPIO28_ADC2_P$42") (pintype "bidirectional"))
    )
    (net (code "28") (name "GP29_A3_SOUND") (class "Default")
      (node (ref "P30") (pin "P$1") (pinfunction "P$1_P$1") (pintype "bidirectional"))
      (node (ref "R61") (pin "1") (pinfunction "1_1") (pintype "passive"))
      (node (ref "U1") (pin "P$43") (pinfunction "GPIO29_ADC3_P$43") (pintype "bidirectional"))
      (node (ref "U11") (pin "1") (pinfunction "1_OUT1_1") (pintype "bidirectional"))
    )
    (net (code "29") (name "GPIO8_US_ECHO") (class "Default")
      (node (ref "R299") (pin "2") (pinfunction "2_2") (pintype "passive"))
      (node (ref "U1") (pin "P$12") (pinfunction "GPIO8_P$12") (pintype "bidirectional"))
    )
    (net (code "30") (name "GPIO9_US_TRIG") (class "Default")
      (node (ref "J14") (pin "P$3") (pinfunction "3_TRIG_P$3") (pintype "bidirectional"))
      (node (ref "U1") (pin "P$13") (pinfunction "GPIO9_P$13") (pintype "bidirectional"))
    )
    (net (code "31") (name "GPIO10_BUZZER") (class "Default")
      (node (ref "R284") (pin "1") (pinfunction "1_1") (pintype "passive"))
      (node (ref "U1") (pin "P$14") (pinfunction "GPIO10_P$14") (pintype "bidirectional"))
    )
    (net (code "32") (name "GPIO11_IR") (class "Default")
      (node (ref "R301") (pin "2") (pinfunction "2_2") (pintype "passive"))
      (node (ref "U1") (pin "P$15") (pinfunction "GPIO11_P$15") (pintype "bidirectional"))
      (node (ref "U309") (pin "3") (pinfunction "P$3_3") (pintype "bidirectional"))
    )
    (net (code "33") (name "GPIO12_RELAY") (class "Default")
      (node (ref "R274") (pin "2") (pinfunction "2_2") (pintype "passive"))
      (node (ref "U1") (pin "P$16") (pinfunction "GPIO12_P$16") (pintype "bidirectional"))
    )
    (net (code "34") (name "GPIO13_SERVO") (class "Default")
      (node (ref "P53") (pin "P$1") (pinfunction "P$1_P$1") (pintype "bidirectional"))
      (node (ref "Q405") (pin "2") (pinfunction "S_2") (pintype "passive"))
      (node (ref "R329") (pin "2") (pinfunction "2_2") (pintype "passive"))
      (node (ref "R422") (pin "1") (pinfunction "1_1") (pintype "passive"))
      (node (ref "U1") (pin "P$17") (pinfunction "GPIO13_P$17") (pintype "bidirectional"))
    )
    (net (code "35") (name "GPIO14_TOUCH") (class "Default")
      (node (ref "P55") (pin "P$1") (pinfunction "P$1_P$1") (pintype "bidirectional"))
      (node (ref "R287") (pin "2") (pinfunction "2_2") (pintype "passive"))
      (node (ref "U1") (pin "P$18") (pinfunction "GPIO14_P$18") (pintype "bidirectional"))
    )
    (net (code "36") (name "GPIO15_VIB") (class "Default")
      (node (ref "R25") (pin "2") (pinfunction "2_2") (pintype "passive"))
      (node (ref "U1") (pin "P$19") (pinfunction "GPIO15_P$19") (pintype "bidirectional"))
    )
    (net (code "37") (name "GPIO18_LED_RED") (class "Default")
      (node (ref "R6") (pin "2") (pinfunction "2_2") (pintype "passive"))
      (node (ref "U1") (pin "P$29") (pinfunction "GPIO18_P$29") (pintype "bidirectional"))
    )
    (net (code "38") (name "GPIO19_LED_GREEN") (class "Default")
      (node (ref "R17") (pin "2") (pinfunction "2_2") (pintype "passive"))
      (node (ref "U1") (pin "P$31") (pinfunction "GPIO19_P$31") (pintype "bidirectional"))
    )
    (net (code "39") (name "GPIO20_LED_YELLOW") (class "Default")
      (node (ref "R22") (pin "2") (pinfunction "2_2") (pintype "passive"))
      (node (ref "U1") (pin "P$32") (pinfunction "GPIO20_P$32") (pintype "bidirectional"))
    )
    (net (code "40") (name "GPIO21_HALL") (class "Default")
      (node (ref "Q7") (pin "2") (pinfunction "S_2") (pintype "passive"))
      (node (ref "R107") (pin "1") (pinfunction "1_1") (pintype "passive"))
      (node (ref "R34") (pin "1") (pinfunction "1_1") (pintype "passive"))
      (node (ref "U1") (pin "P$33") (pinfunction "GPIO21_P$33") (pintype "bidirectional"))
    )
    (net (code "41") (name "GPIO22_RGB") (class "Default")
      (node (ref "R54") (pin "1") (pinfunction "1_1") (pintype "passive"))
      (node (ref "U1") (pin "P$34") (pinfunction "GPIO22_P$34") (pintype "bidirectional"))
    )
    (net (code "42") (name "GPIO23_RGB_EN") (class "Default")
      (node (ref "R191") (pin "1") (pinfunction "1_1") (pintype "passive"))
      (node (ref "U1") (pin "P$35") (pinfunction "GPIO23_P$35") (pintype "bidirectional"))
    )
    (net (code "43") (name "GPIO24_TP_RST") (class "Default")
      (node (ref "FPC1") (pin "P$6") (pinfunction "YU/CTP_RST_P$6") (pintype "bidirectional"))
      (node (ref "P18") (pin "P$1") (pinfunction "P$1_P$1") (pintype "bidirectional"))
      (node (ref "U1") (pin "P$36") (pinfunction "GPIO24_P$36") (pintype "bidirectional"))
    )
    (net (code "44") (name "GPIO25_TP_INT") (class "Default")
      (node (ref "FPC1") (pin "P$5") (pinfunction "XL/CTP_INT_P$5") (pintype "bidirectional"))
      (node (ref "P17") (pin "P$1") (pinfunction "P$1_P$1") (pintype "bidirectional"))
      (node (ref "U1") (pin "P$37") (pinfunction "GPIO25_P$37") (pintype "bidirectional"))
    )
    (net (code "45") (name "IO_LED_VCC") (class "Default")
      (node (ref "C27") (pin "1") (pinfunction "1_1") (pintype "passive"))
      (node (ref "C28") (pin "1") (pinfunction "1_1") (pintype "passive"))
      (node (ref "C57") (pin "1") (pinfunction "1_1") (pintype "passive"))
      (node (ref "D012") (pin "1") (pinfunction "1_VDD_1") (pintype "bidirectional"))
      (node (ref "D019") (pin "1") (pinfunction "1_VDD_1") (pintype "bidirectional"))
      (node (ref "D021") (pin "1") (pinfunction "1_VDD_1") (pintype "bidirectional"))
      (node (ref "D022") (pin "1") (pinfunction "1_VDD_1") (pintype "bidirectional"))
      (node (ref "D023") (pin "1") (pinfunction "1_VDD_1") (pintype "bidirectional"))
      (node (ref "D024") (pin "1") (pinfunction "1_VDD_1") (pintype "bidirectional"))
      (node (ref "D025") (pin "1") (pinfunction "1_VDD_1") (pintype "bidirectional"))
      (node (ref "D026") (pin "1") (pinfunction "1_VDD_1") (pintype "bidirectional"))
      (node (ref "D027") (pin "1") (pinfunction "1_VDD_1") (pintype "bidirectional"))
      (node (ref "D028") (pin "1") (pinfunction "1_VDD_1") (pintype "bidirectional"))
      (node (ref "D029") (pin "1") (pinfunction "1_VDD_1") (pintype "bidirectional"))
      (node (ref "D030") (pin "1") (pinfunction "1_VDD_1") (pintype "bidirectional"))
      (node (ref "D031") (pin "1") (pinfunction "1_VDD_1") (pintype "bidirectional"))
      (node (ref "D032") (pin "1") (pinfunction "1_VDD_1") (pintype "bidirectional"))
      (node (ref "D033") (pin "1") (pinfunction "1_VDD_1") (pintype "bidirectional"))
      (node (ref "D183") (pin "1") (pinfunction "1_VDD_1") (pintype "bidirectional"))
      (node (ref "D184") (pin "1") (pinfunction "1_VDD_1") (pintype "bidirectional"))
      (node (ref "D185") (pin "1") (pinfunction "1_VDD_1") (pintype "bidirectional"))
      (node (ref "D186") (pin "1") (pinfunction "1_VDD_1") (pintype "bidirectional"))
      (node (ref "D187") (pin "1") (pinfunction "1_VDD_1") (pintype "bidirectional"))
      (node (ref "J110") (pin "1") (pinfunction "1_2B_1") (pintype "bidirectional"))
      (node (ref "U10") (pin "5") (pinfunction "VCC_5") (pintype "bidirectional"))
    )
    (net (code "46") (name "LED_K") (class "Default")
      (node (ref "FPC1") (pin "P$9") (pinfunction "BL_K_P$9") (pintype "bidirectional"))
      (node (ref "P14") (pin "P$1") (pinfunction "P$1_P$1") (pintype "bidirectional"))
      (node (ref "R40") (pin "2") (pinfunction "2_2") (pintype "passive"))
    )
    (net (code "47") (name "Net-(BUZ1-1+)") (class "Default")
      (node (ref "BUZ1") (pin "1") (pinfunction "1+_1") (pintype "bidirectional"))
      (node (ref "D004") (pin "-") (pinfunction "-_-") (pintype "passive"))
      (node (ref "R303") (pin "2") (pinfunction "2_2") (pintype "passive"))
    )
    (net (code "48") (name "Net-(BUZ1-2-)") (class "Default")
      (node (ref "BUZ1") (pin "2") (pinfunction "2-_2") (pintype "bidirectional"))
      (node (ref "D004") (pin "+") (pinfunction "+_+") (pintype "passive"))
      (node (ref "Q103") (pin "3") (pinfunction "C_3") (pintype "passive"))
    )
    (net (code "49") (name "Net-(C32-Pad2)") (class "Default")
      (node (ref "C32") (pin "2") (pinfunction "2_2") (pintype "passive"))
      (node (ref "J313") (pin "P$1") (pinfunction "P$1_P$1") (pintype "bidirectional"))
      (node (ref "R283") (pin "2") (pinfunction "2_2") (pintype "passive"))
    )
    (net (code "50") (name "Net-(D005-A)") (class "Default")
      (node (ref "D005") (pin "1") (pinfunction "A_1") (pintype "passive"))
      (node (ref "R20") (pin "2") (pinfunction "2_2") (pintype "passive"))
    )
    (net (code "51") (name "Net-(D005-C)") (class "Default")
      (node (ref "D005") (pin "2") (pinfunction "C_2") (pintype "passive"))
      (node (ref "Q2") (pin "3") (pinfunction "C_3") (pintype "passive"))
    )
    (net (code "52") (name "Net-(D006-A)") (class "Default")
      (node (ref "D006") (pin "1") (pinfunction "A_1") (pintype "passive"))
      (node (ref "R23") (pin "2") (pinfunction "2_2") (pintype "passive"))
    )
    (net (code "53") (name "Net-(D006-C)") (class "Default")
      (node (ref "D006") (pin "2") (pinfunction "C_2") (pintype "passive"))
      (node (ref "Q3") (pin "3") (pinfunction "C_3") (pintype "passive"))
    )
    (net (code "54") (name "Net-(D11-A)") (class "Default")
      (node (ref "D11") (pin "1") (pinfunction "A_1") (pintype "passive"))
      (node (ref "R7") (pin "2") (pinfunction "2_2") (pintype "passive"))
    )
    (net (code "55") (name "Net-(D11-C)") (class "Default")
      (node (ref "D11") (pin "2") (pinfunction "C_2") (pintype "passive"))
      (node (ref "Q1") (pin "3") (pinfunction "C_3") (pintype "passive"))
    )
    (net (code "56") (name "Net-(D012-2_DOUT)") (class "Default")
      (node (ref "D012") (pin "2") (pinfunction "2_DOUT_2") (pintype "bidirectional"))
      (node (ref "D019") (pin "4") (pinfunction "4_DIN_4") (pintype "bidirectional"))
    )
    (net (code "57") (name "Net-(D012-4_DIN)") (class "Default")
      (node (ref "D012") (pin "4") (pinfunction "4_DIN_4") (pintype "bidirectional"))
      (node (ref "D187") (pin "2") (pinfunction "2_DOUT_2") (pintype "bidirectional"))
    )
    (net (code "58") (name "Net-(D019-2_DOUT)") (class "Default")
      (node (ref "D019") (pin "2") (pinfunction "2_DOUT_2") (pintype "bidirectional"))
      (node (ref "D021") (pin "4") (pinfunction "4_DIN_4") (pintype "bidirectional"))
    )
    (net (code "59") (name "Net-(D021-2_DOUT)") (class "Default")
      (node (ref "D021") (pin "2") (pinfunction "2_DOUT_2") (pintype "bidirectional"))
      (node (ref "D022") (pin "4") (pinfunction "4_DIN_4") (pintype "bidirectional"))
    )
    (net (code "60") (name "Net-(D022-2_DOUT)") (class "Default")
      (node (ref "D022") (pin "2") (pinfunction "2_DOUT_2") (pintype "bidirectional"))
      (node (ref "D023") (pin "4") (pinfunction "4_DIN_4") (pintype "bidirectional"))
    )
    (net (code "61") (name "Net-(D023-2_DOUT)") (class "Default")
      (node (ref "D023") (pin "2") (pinfunction "2_DOUT_2") (pintype "bidirectional"))
      (node (ref "D024") (pin "4") (pinfunction "4_DIN_4") (pintype "bidirectional"))
    )
    (net (code "62") (name "Net-(D024-2_DOUT)") (class "Default")
      (node (ref "D024") (pin "2") (pinfunction "2_DOUT_2") (pintype "bidirectional"))
      (node (ref "D025") (pin "4") (pinfunction "4_DIN_4") (pintype "bidirectional"))
    )
    (net (code "63") (name "Net-(D025-2_DOUT)") (class "Default")
      (node (ref "D025") (pin "2") (pinfunction "2_DOUT_2") (pintype "bidirectional"))
      (node (ref "D026") (pin "4") (pinfunction "4_DIN_4") (pintype "bidirectional"))
    )
    (net (code "64") (name "Net-(D026-2_DOUT)") (class "Default")
      (node (ref "D026") (pin "2") (pinfunction "2_DOUT_2") (pintype "bidirectional"))
      (node (ref "D027") (pin "4") (pinfunction "4_DIN_4") (pintype "bidirectional"))
    )
    (net (code "65") (name "Net-(D027-2_DOUT)") (class "Default")
      (node (ref "D027") (pin "2") (pinfunction "2_DOUT_2") (pintype "bidirectional"))
      (node (ref "D028") (pin "4") (pinfunction "4_DIN_4") (pintype "bidirectional"))
    )
    (net (code "66") (name "Net-(D028-2_DOUT)") (class "Default")
      (node (ref "D028") (pin "2") (pinfunction "2_DOUT_2") (pintype "bidirectional"))
      (node (ref "D029") (pin "4") (pinfunction "4_DIN_4") (pintype "bidirectional"))
    )
    (net (code "67") (name "Net-(D029-2_DOUT)") (class "Default")
      (node (ref "D029") (pin "2") (pinfunction "2_DOUT_2") (pintype "bidirectional"))
      (node (ref "D030") (pin "4") (pinfunction "4_DIN_4") (pintype "bidirectional"))
    )
    (net (code "68") (name "Net-(D030-2_DOUT)") (class "Default")
      (node (ref "D030") (pin "2") (pinfunction "2_DOUT_2") (pintype "bidirectional"))
      (node (ref "D031") (pin "4") (pinfunction "4_DIN_4") (pintype "bidirectional"))
    )
    (net (code "69") (name "Net-(D031-2_DOUT)") (class "Default")
      (node (ref "D031") (pin "2") (pinfunction "2_DOUT_2") (pintype "bidirectional"))
      (node (ref "D032") (pin "4") (pinfunction "4_DIN_4") (pintype "bidirectional"))
    )
    (net (code "70") (name "Net-(D032-2_DOUT)") (class "Default")
      (node (ref "D032") (pin "2") (pinfunction "2_DOUT_2") (pintype "bidirectional"))
      (node (ref "D033") (pin "4") (pinfunction "4_DIN_4") (pintype "bidirectional"))
    )
    (net (code "71") (name "Net-(D143-2_K)") (class "Default")
      (node (ref "D143") (pin "2") (pinfunction "2_K_2") (pintype "passive"))
      (node (ref "R622") (pin "1") (pinfunction "1_1") (pintype "passive"))
    )
    (net (code "72") (name "Net-(D183-2_DOUT)") (class "Default")
      (node (ref "D183") (pin "2") (pinfunction "2_DOUT_2") (pintype "bidirectional"))
      (node (ref "D184") (pin "4") (pinfunction "4_DIN_4") (pintype "bidirectional"))
    )
    (net (code "73") (name "Net-(D184-2_DOUT)") (class "Default")
      (node (ref "D184") (pin "2") (pinfunction "2_DOUT_2") (pintype "bidirectional"))
      (node (ref "D185") (pin "4") (pinfunction "4_DIN_4") (pintype "bidirectional"))
    )
    (net (code "74") (name "Net-(D185-2_DOUT)") (class "Default")
      (node (ref "D185") (pin "2") (pinfunction "2_DOUT_2") (pintype "bidirectional"))
      (node (ref "D186") (pin "4") (pinfunction "4_DIN_4") (pintype "bidirectional"))
    )
    (net (code "75") (name "Net-(D186-2_DOUT)") (class "Default")
      (node (ref "D186") (pin "2") (pinfunction "2_DOUT_2") (pintype "bidirectional"))
      (node (ref "D187") (pin "4") (pinfunction "4_DIN_4") (pintype "bidirectional"))
    )
    (net (code "76") (name "Net-(J2-H-Pad5)") (class "Default")
      (node (ref "J2") (pin "5") (pinfunction "H_5") (pintype "bidirectional"))
      (node (ref "R35") (pin "2") (pinfunction "2_2") (pintype "passive"))
    )
    (net (code "77") (name "Net-(J3-+)") (class "Default")
      (node (ref "C65") (pin "2") (pinfunction "2_2") (pintype "passive"))
      (node (ref "C67") (pin "2") (pinfunction "2_2") (pintype "passive"))
      (node (ref "J3") (pin "1") (pinfunction "+_1") (pintype "bidirectional"))
      (node (ref "R56") (pin "1") (pinfunction "1_1") (pintype "passive"))
      (node (ref "R58") (pin "1") (pinfunction "1_1") (pintype "passive"))
    )
    (net (code "78") (name "Net-(J14-2_ECHO)") (class "Default")
      (node (ref "J14") (pin "P$2") (pinfunction "2_ECHO_P$2") (pintype "bidirectional"))
      (node (ref "R299") (pin "1") (pinfunction "1_1") (pintype "passive"))
    )
    (net (code "79") (name "Net-(J110-2_COM2)") (class "Default")
      (node (ref "C30") (pin "1") (pinfunction "1_1") (pintype "passive"))
      (node (ref "C90") (pin "1") (pinfunction "1_1") (pintype "passive"))
      (node (ref "J110") (pin "2") (pinfunction "2_COM2_2") (pintype "bidirectional"))
      (node (ref "J110") (pin "5") (pinfunction "5_COM1_5") (pintype "bidirectional"))
      (node (ref "P70") (pin "P$1") (pinfunction "P$1_P$1") (pintype "bidirectional"))
      (node (ref "R118") (pin "2") (pinfunction "2_2") (pintype "passive"))
      (node (ref "U34") (pin "1") (pinfunction "1_OUT_1") (pintype "bidirectional"))
    )
    (net (code "80") (name "Net-(K1-PadP$2)") (class "Default")
      (node (ref "K1") (pin "P$2") (pinfunction "P$2_P$2") (pintype "bidirectional"))
      (node (ref "R652") (pin "1") (pinfunction "1_1") (pintype "passive"))
    )
    (net (code "81") (name "Net-(K2-PadP$2)") (class "Default")
      (node (ref "K2") (pin "P$2") (pinfunction "P$2_P$2") (pintype "bidirectional"))
      (node (ref "R653") (pin "1") (pinfunction "1_1") (pintype "passive"))
    )
    (net (code "82") (name "Net-(K3-PadP$2)") (class "Default")
      (node (ref "K3") (pin "P$2") (pinfunction "P$2_P$2") (pintype "bidirectional"))
      (node (ref "R654") (pin "1") (pinfunction "1_1") (pintype "passive"))
    )
    (net (code "83") (name "Net-(K4-PadP$2)") (class "Default")
      (node (ref "K4") (pin "P$2") (pinfunction "P$2_P$2") (pintype "bidirectional"))
      (node (ref "R655") (pin "1") (pinfunction "1_1") (pintype "passive"))
    )
    (net (code "84") (name "Net-(L1-2)") (class "Default")
      (node (ref "L1") (pin "P$2") (pinfunction "2_P$2") (pintype "passive"))
      (node (ref "U1") (pin "P$48") (pinfunction "VREG_LX_P$48") (pintype "bidirectional"))
    )
    (net (code "85") (name "Net-(LED1-Pad+)") (class "Default")
      (node (ref "LED1") (pin "+") (pinfunction "+_+") (pintype "passive"))
      (node (ref "R24") (pin "1") (pinfunction "1_1") (pintype "passive"))
    )
    (net (code "86") (name "Net-(P101-P$1)") (class "Default")
      (node (ref "C212") (pin "2") (pinfunction "2_2") (pintype "passive"))
      (node (ref "P101") (pin "1") (pinfunction "P$1_1") (pintype "bidirectional"))
      (node (ref "U123") (pin "3") (pinfunction "IN_3") (pintype "bidirectional"))
    )
    (net (code "87") (name "Net-(Q1-B)") (class "Default")
      (node (ref "Q1") (pin "1") (pinfunction "B_1") (pintype "passive"))
      (node (ref "R4") (pin "2") (pinfunction "2_2") (pintype "passive"))
      (node (ref "R6") (pin "1") (pinfunction "1_1") (pintype "passive"))
    )
    (net (code "88") (name "Net-(Q2-B)") (class "Default")
      (node (ref "Q2") (pin "1") (pinfunction "B_1") (pintype "passive"))
      (node (ref "R13") (pin "2") (pinfunction "2_2") (pintype "passive"))
      (node (ref "R17") (pin "1") (pinfunction "1_1") (pintype "passive"))
    )
    (net (code "89") (name "Net-(Q3-B)") (class "Default")
      (node (ref "Q3") (pin "1") (pinfunction "B_1") (pintype "passive"))
      (node (ref "R21") (pin "2") (pinfunction "2_2") (pintype "passive"))
      (node (ref "R22") (pin "1") (pinfunction "1_1") (pintype "passive"))
    )
    (net (code "90") (name "Net-(Q5-B)") (class "Default")
      (node (ref "Q5") (pin "1") (pinfunction "B_1") (pintype "passive"))
      (node (ref "R41") (pin "1") (pinfunction "1_1") (pintype "passive"))
      (node (ref "R42") (pin "1") (pinfunction "1_1") (pintype "passive"))
    )
    (net (code "91") (name "Net-(Q5-C)") (class "Default")
      (node (ref "Q5") (pin "3") (pinfunction "C_3") (pintype "passive"))
      (node (ref "R40") (pin "1") (pinfunction "1_1") (pintype "passive"))
    )
    (net (code "92") (name "Net-(Q6-B)") (class "Default")
      (node (ref "C65") (pin "1") (pinfunction "1_1") (pintype "passive"))
      (node (ref "Q6") (pin "1") (pinfunction "B_1") (pintype "passive"))
      (node (ref "R57") (pin "1") (pinfunction "1_1") (pintype "passive"))
    )
    (net (code "93") (name "Net-(Q6-C)") (class "Default")
      (node (ref "C68") (pin "2") (pinfunction "2_2") (pintype "passive"))
      (node (ref "Q6") (pin "3") (pinfunction "C_3") (pintype "passive"))
      (node (ref "R59") (pin "1") (pinfunction "1_1") (pintype "passive"))
      (node (ref "U11") (pin "2") (pinfunction "2_IN1-_2") (pintype "bidirectional"))
    )
    (net (code "94") (name "Net-(Q103-B)") (class "Default")
      (node (ref "Q103") (pin "1") (pinfunction "B_1") (pintype "passive"))
      (node (ref "R284") (pin "2") (pinfunction "2_2") (pintype "passive"))
      (node (ref "R302") (pin "2") (pinfunction "2_2") (pintype "passive"))
    )
    (net (code "95") (name "Net-(Q104-B)") (class "Default")
      (node (ref "Q104") (pin "1") (pinfunction "B_1") (pintype "passive"))
      (node (ref "R282") (pin "2") (pinfunction "2_2") (pintype "passive"))
    )
    (net (code "96") (name "Net-(Q104-C)") (class "Default")
      (node (ref "J313") (pin "P$2") (pinfunction "P$2_P$2") (pintype "bidirectional"))
      (node (ref "Q104") (pin "3") (pinfunction "C_3") (pintype "passive"))
    )
    (net (code "97") (name "Net-(Q115-B)") (class "Default")
      (node (ref "Q115") (pin "1") (pinfunction "B_1") (pintype "passive"))
      (node (ref "R273") (pin "2") (pinfunction "2_2") (pintype "passive"))
      (node (ref "R274") (pin "1") (pinfunction "1_1") (pintype "passive"))
    )
    (net (code "98") (name "Net-(R25-Pad1)") (class "Default")
      (node (ref "R25") (pin "1") (pinfunction "1_1") (pintype "passive"))
      (node (ref "R280") (pin "2") (pinfunction "2_2") (pintype "passive"))
      (node (ref "R282") (pin "1") (pinfunction "1_1") (pintype "passive"))
    )
    (net (code "99") (name "Net-(R62-3)") (class "Default")
      (node (ref "R62") (pin "2") (pinfunction "3_2") (pintype "passive"))
      (node (ref "U11") (pin "3") (pinfunction "3_IN1+_3") (pintype "bidirectional"))
    )
    (net (code "100") (name "Net-(U1-GPIO2)") (class "Default")
      (node (ref "R26") (pin "1") (pinfunction "1_1") (pintype "passive"))
      (node (ref "U1") (pin "P$4") (pinfunction "GPIO2_P$4") (pintype "bidirectional"))
    )
    (net (code "101") (name "Net-(U1-GPIO3)") (class "Default")
      (node (ref "R27") (pin "1") (pinfunction "1_1") (pintype "passive"))
      (node (ref "U1") (pin "P$5") (pinfunction "GPIO3_P$5") (pintype "bidirectional"))
    )
    (net (code "102") (name "Net-(U1-GPIO4)") (class "Default")
      (node (ref "R28") (pin "1") (pinfunction "1_1") (pintype "passive"))
      (node (ref "U1") (pin "P$7") (pinfunction "GPIO4_P$7") (pintype "bidirectional"))
    )
    (net (code "103") (name "Net-(U1-GPIO5)") (class "Default")
      (node (ref "R29") (pin "1") (pinfunction "1_1") (pintype "passive"))
      (node (ref "U1") (pin "P$8") (pinfunction "GPIO5_P$8") (pintype "bidirectional"))
    )
    (net (code "104") (name "Net-(U1-VREG_AVDD)") (class "Default")
      (node (ref "C17") (pin "1") (pinfunction "1_1") (pintype "passive"))
      (node (ref "R16") (pin "2") (pinfunction "2_2") (pintype "passive"))
      (node (ref "U1") (pin "P$46") (pinfunction "VREG_AVDD_P$46") (pintype "bidirectional"))
    )
    (net (code "105") (name "Net-(U7-ADDR)") (class "Default")
      (node (ref "R12") (pin "1") (pinfunction "1_1") (pintype "passive"))
      (node (ref "R15") (pin "2") (pinfunction "2_2") (pintype "passive"))
      (node (ref "U7") (pin "2") (pinfunction "ADDR_2") (pintype "bidirectional"))
    )
    (net (code "106") (name "Net-(U7-DVI)") (class "Default")
      (node (ref "C3") (pin "2") (pinfunction "2_2") (pintype "passive"))
      (node (ref "R9") (pin "2") (pinfunction "2_2") (pintype "passive"))
      (node (ref "U7") (pin "5") (pinfunction "DVI_5") (pintype "bidirectional"))
    )
    (net (code "107") (name "Net-(U8-EN)") (class "Default")
      (node (ref "C55") (pin "2") (pinfunction "2_2") (pintype "passive"))
      (node (ref "C56") (pin "2") (pinfunction "2_2") (pintype "passive"))
      (node (ref "D3") (pin "+") (pinfunction "+_+") (pintype "passive"))
      (node (ref "FUSE") (pin "2") (pinfunction "2_2") (pintype "passive"))
      (node (ref "L3") (pin "1") (pinfunction "1_1") (pintype "passive"))
      (node (ref "U8") (pin "4") (pinfunction "EN_4") (pintype "bidirectional"))
      (node (ref "U8") (pin "5") (pinfunction "IN_5") (pintype "bidirectional"))
    )
    (net (code "108") (name "Net-(U8-FB)") (class "Default")
      (node (ref "R30") (pin "2") (pinfunction "2_2") (pintype "passive"))
      (node (ref "R32") (pin "1") (pinfunction "1_1") (pintype "passive"))
      (node (ref "U8") (pin "3") (pinfunction "FB_3") (pintype "bidirectional"))
    )
    (net (code "109") (name "Net-(U8-SW)") (class "Default")
      (node (ref "D10") (pin "A") (pinfunction "A_A") (pintype "passive"))
      (node (ref "L3") (pin "2") (pinfunction "2_2") (pintype "passive"))
      (node (ref "U8") (pin "1") (pinfunction "SW_1") (pintype "bidirectional"))
    )
    (net (code "110") (name "Net-(U10-IN_A)") (class "Default")
      (node (ref "R54") (pin "2") (pinfunction "2_2") (pintype "passive"))
      (node (ref "U10") (pin "2") (pinfunction "IN_A_2") (pintype "bidirectional"))
    )
    (net (code "111") (name "Net-(U12-CS)") (class "Default")
      (node (ref "R84") (pin "2") (pinfunction "2_2") (pintype "passive"))
      (node (ref "U12") (pin "12") (pinfunction "CS_12") (pintype "bidirectional"))
    )
    (net (code "112") (name "Net-(U12-SCX)") (class "Default")
      (node (ref "R83") (pin "2") (pinfunction "2_2") (pintype "passive"))
      (node (ref "U12") (pin "3") (pinfunction "SCX_3") (pintype "bidirectional"))
    )
    (net (code "113") (name "Net-(U12-SDO)") (class "Default")
      (node (ref "R85") (pin "2") (pinfunction "2_2") (pintype "passive"))
      (node (ref "U12") (pin "1") (pinfunction "SDO_1") (pintype "bidirectional"))
    )
    (net (code "114") (name "Net-(U12-SDX)") (class "Default")
      (node (ref "R82") (pin "2") (pinfunction "2_2") (pintype "passive"))
      (node (ref "U12") (pin "2") (pinfunction "SDX_2") (pintype "bidirectional"))
    )
    (net (code "115") (name "Net-(U30-BF)") (class "Default")
      (node (ref "R3") (pin "2") (pinfunction "2_2") (pintype "passive"))
      (node (ref "R76") (pin "1") (pinfunction "1_1") (pintype "passive"))
      (node (ref "U30") (pin "3") (pinfunction "BF_3") (pintype "bidirectional"))
    )
    (net (code "116") (name "Net-(U30-BS)") (class "Default")
      (node (ref "C9") (pin "2") (pinfunction "2_2") (pintype "passive"))
      (node (ref "U30") (pin "1") (pinfunction "BS_1") (pintype "bidirectional"))
    )
    (net (code "117") (name "Net-(U30-EN)") (class "Default")
      (node (ref "R115") (pin "1") (pinfunction "1_1") (pintype "passive"))
      (node (ref "R191") (pin "2") (pinfunction "2_2") (pintype "passive"))
      (node (ref "U30") (pin "4") (pinfunction "EN_4") (pintype "bidirectional"))
    )
    (net (code "118") (name "Net-(U30-SW)") (class "Default")
      (node (ref "C9") (pin "1") (pinfunction "1_1") (pintype "passive"))
      (node (ref "L2") (pin "1") (pinfunction "1_1") (pintype "bidirectional"))
      (node (ref "U30") (pin "6") (pinfunction "SW_6") (pintype "bidirectional"))
    )
    (net (code "119") (name "Net-(U34-3_SET)") (class "Default")
      (node (ref "R117") (pin "1") (pinfunction "1_1") (pintype "passive"))
      (node (ref "U34") (pin "3") (pinfunction "3_SET_3") (pintype "bidirectional"))
    )
    (net (code "120") (name "Net-(U34-4_EN)") (class "Default")
      (node (ref "R116") (pin "1") (pinfunction "1_1") (pintype "passive"))
      (node (ref "U34") (pin "4") (pinfunction "4_EN_4") (pintype "bidirectional"))
    )
    (net (code "121") (name "Net-(U41-IADJ)") (class "Default")
      (node (ref "R190") (pin "1") (pinfunction "1_1") (pintype "passive"))
      (node (ref "U41") (pin "3") (pinfunction "IADJ_3") (pintype "bidirectional"))
    )
    (net (code "122") (name "Net-(U41-VOUT)") (class "Default")
      (node (ref "C44") (pin "1") (pinfunction "1_1") (pintype "passive"))
      (node (ref "FB1") (pin "2") (pinfunction "2_2") (pintype "passive"))
      (node (ref "FB2") (pin "1") (pinfunction "1_1") (pintype "passive"))
      (node (ref "U41") (pin "1") (pinfunction "VOUT_1") (pintype "bidirectional"))
    )
    (net (code "123") (name "Net-(U123-AHLB)") (class "Default")
      (node (ref "R288") (pin "1") (pinfunction "1_1") (pintype "passive"))
      (node (ref "U123") (pin "4") (pinfunction "AHLB_4") (pintype "bidirectional"))
      (node (ref "U123") (pin "6") (pinfunction "TOG_6") (pintype "bidirectional"))
    )
    (net (code "124") (name "Net-(U123-OUT)") (class "Default")
      (node (ref "R286") (pin "1") (pinfunction "1_1") (pintype "passive"))
      (node (ref "R287") (pin "1") (pinfunction "1_1") (pintype "passive"))
      (node (ref "U123") (pin "1") (pinfunction "OUT_1") (pintype "bidirectional"))
    )
    (net (code "125") (name "Net-(X1-XOUT)") (class "Default")
      (node (ref "C2") (pin "1") (pinfunction "1_1") (pintype "passive"))
      (node (ref "R8") (pin "2") (pinfunction "2_2") (pintype "passive"))
      (node (ref "X1") (pin "3") (pinfunction "XOUT_3") (pintype "bidirectional"))
    )
    (net (code "126") (name "QSPI_SCLK") (class "Default")
      (node (ref "U1") (pin "P$56") (pinfunction "QSPI_SCLK_P$56") (pintype "bidirectional"))
      (node (ref "U2") (pin "P$6") (pinfunction "SCLK_P$6") (pintype "bidirectional"))
      (node (ref "U3") (pin "6") (pinfunction "CLK_6") (pintype "bidirectional"))
    )
    (net (code "127") (name "QSPI_SD0") (class "Default")
      (node (ref "U1") (pin "P$57") (pinfunction "QSPI_SD0_P$57") (pintype "bidirectional"))
      (node (ref "U2") (pin "P$5") (pinfunction "SI/SIO0_P$5") (pintype "bidirectional"))
      (node (ref "U3") (pin "5") (pinfunction "DI(IO0)_5") (pintype "bidirectional"))
    )
    (net (code "128") (name "QSPI_SD1") (class "Default")
      (node (ref "U1") (pin "P$59") (pinfunction "QSPI_SD1_P$59") (pintype "bidirectional"))
      (node (ref "U2") (pin "P$2") (pinfunction "SO/SIO1_P$2") (pintype "bidirectional"))
      (node (ref "U3") (pin "2") (pinfunction "DO(IO1)_2") (pintype "bidirectional"))
    )
    (net (code "129") (name "QSPI_SD2") (class "Default")
      (node (ref "U1") (pin "P$58") (pinfunction "QSPI_SD2_P$58") (pintype "bidirectional"))
      (node (ref "U2") (pin "P$3") (pinfunction "SIO2_P$3") (pintype "bidirectional"))
      (node (ref "U3") (pin "3") (pinfunction "/WP(IO2)_3") (pintype "bidirectional"))
    )
    (net (code "130") (name "QSPI_SD3") (class "Default")
      (node (ref "U1") (pin "P$55") (pinfunction "QSPI_SD3_P$55") (pintype "bidirectional"))
      (node (ref "U2") (pin "P$7") (pinfunction "SIO3_P$7") (pintype "bidirectional"))
      (node (ref "U3") (pin "7") (pinfunction "/HOLD(IO3)_7") (pintype "bidirectional"))
    )
    (net (code "131") (name "QSPI_SS") (class "Default")
      (node (ref "R1") (pin "1") (pinfunction "1_1") (pintype "passive"))
      (node (ref "R2") (pin "1") (pinfunction "1_1") (pintype "passive"))
      (node (ref "U1") (pin "P$60") (pinfunction "QSPI_SS_P$60") (pintype "bidirectional"))
      (node (ref "U3") (pin "1") (pinfunction "/CS_1") (pintype "bidirectional"))
    )
    (net (code "132") (name "SERVO") (class "Default")
      (node (ref "J1") (pin "1") (pinfunction "1_1") (pintype "bidirectional"))
      (node (ref "J15") (pin "1") (pinfunction "G_1") (pintype "bidirectional"))
      (node (ref "P12") (pin "P$1") (pinfunction "P$1_P$1") (pintype "bidirectional"))
      (node (ref "Q405") (pin "3") (pinfunction "D_3") (pintype "passive"))
      (node (ref "R329") (pin "1") (pinfunction "1_1") (pintype "passive"))
      (node (ref "R423") (pin "2") (pinfunction "2_2") (pintype "passive"))
    )
    (net (code "133") (name "SWCLK") (class "Default")
      (node (ref "P5") (pin "P$1") (pinfunction "P$1_P$1") (pintype "bidirectional"))
      (node (ref "U1") (pin "P$24") (pinfunction "SWCLK_P$24") (pintype "bidirectional"))
    )
    (net (code "134") (name "SWDIO") (class "Default")
      (node (ref "P6") (pin "P$1") (pinfunction "P$1_P$1") (pintype "bidirectional"))
      (node (ref "U1") (pin "P$25") (pinfunction "SWD_P$25") (pintype "bidirectional"))
    )
    (net (code "135") (name "TFT_3V3") (class "Default")
      (node (ref "C47") (pin "2") (pinfunction "2_2") (pintype "passive"))
      (node (ref "C48") (pin "2") (pinfunction "2_2") (pintype "passive"))
      (node (ref "FB3") (pin "2") (pinfunction "2_2") (pintype "passive"))
      (node (ref "FPC1") (pin "P$10") (pinfunction "BL_A_P$10") (pintype "bidirectional"))
      (node (ref "FPC1") (pin "P$15") (pinfunction "VCC_P$15") (pintype "bidirectional"))
      (node (ref "FPC1") (pin "P$2") (pinfunction "VCC_P$2") (pintype "bidirectional"))
      (node (ref "P23") (pin "P$1") (pinfunction "P$1_P$1") (pintype "bidirectional"))
      (node (ref "R43") (pin "2") (pinfunction "2_2") (pintype "passive"))
      (node (ref "R44") (pin "2") (pinfunction "2_2") (pintype "passive"))
      (node (ref "R45") (pin "2") (pinfunction "2_2") (pintype "passive"))
      (node (ref "R46") (pin "2") (pinfunction "2_2") (pintype "passive"))
      (node (ref "R47") (pin "2") (pinfunction "2_2") (pintype "passive"))
    )
    (net (code "136") (name "TFT_RST") (class "Default")
      (node (ref "C49") (pin "2") (pinfunction "2_2") (pintype "passive"))
      (node (ref "D001") (pin "+") (pinfunction "+_+") (pintype "passive"))
      (node (ref "FPC1") (pin "P$11") (pinfunction "RESET_P$11") (pintype "bidirectional"))
      (node (ref "P13") (pin "P$1") (pinfunction "P$1_P$1") (pintype "bidirectional"))
      (node (ref "R47") (pin "1") (pinfunction "1_1") (pintype "passive"))
    )
    (net (code "137") (name "TYPE-C_N") (class "Default")
      (node (ref "J5") (pin "1") (pinfunction "1_1") (pintype "bidirectional"))
      (node (ref "J8") (pin "3") (pinfunction "3_3") (pintype "bidirectional"))
      (node (ref "R10") (pin "1") (pinfunction "1_1") (pintype "passive"))
    )
    (net (code "138") (name "TYPE-C_P") (class "Default")
      (node (ref "J6") (pin "1") (pinfunction "1_1") (pintype "bidirectional"))
      (node (ref "J8") (pin "2") (pinfunction "2_2") (pintype "bidirectional"))
      (node (ref "R11") (pin "1") (pinfunction "1_1") (pintype "passive"))
    )
    (net (code "139") (name "USB_D+") (class "Default")
      (node (ref "R11") (pin "2") (pinfunction "2_2") (pintype "passive"))
      (node (ref "U1") (pin "P$52") (pinfunction "USB_DP_P$52") (pintype "bidirectional"))
    )
    (net (code "140") (name "USB_D-") (class "Default")
      (node (ref "R10") (pin "2") (pinfunction "2_2") (pintype "passive"))
      (node (ref "U1") (pin "P$51") (pinfunction "USB_DM_P$51") (pintype "bidirectional"))
    )
    (net (code "141") (name "VBUS") (class "Default")
      (node (ref "C5") (pin "2") (pinfunction "2_2") (pintype "passive"))
      (node (ref "C51") (pin "1") (pinfunction "1_1") (pintype "passive"))
      (node (ref "FB1") (pin "1") (pinfunction "1_1") (pintype "passive"))
      (node (ref "FUSE") (pin "1") (pinfunction "1_1") (pintype "passive"))
      (node (ref "J4") (pin "1") (pinfunction "1_1") (pintype "bidirectional"))
      (node (ref "J8") (pin "1") (pinfunction "1_1") (pintype "bidirectional"))
      (node (ref "U41") (pin "4") (pinfunction "EN_4") (pintype "bidirectional"))
      (node (ref "U41") (pin "5") (pinfunction "VIN_5") (pintype "bidirectional"))
    )
    (net (code "142") (name "VCC3V3") (class "Default")
      (node (ref "C29") (pin "1") (pinfunction "1_1") (pintype "passive"))
      (node (ref "C409") (pin "2") (pinfunction "2_2") (pintype "passive"))
      (node (ref "C412") (pin "2") (pinfunction "2_2") (pintype "passive"))
      (node (ref "C414") (pin "1") (pinfunction "1_1") (pintype "passive"))
      (node (ref "D143") (pin "1") (pinfunction "1_A_1") (pintype "passive"))
      (node (ref "FB4") (pin "1") (pinfunction "1_1") (pintype "passive"))
      (node (ref "L401") (pin "2") (pinfunction "2_2") (pintype "bidirectional"))
      (node (ref "P1") (pin "P$1") (pinfunction "P$1_P$1") (pintype "bidirectional"))
      (node (ref "P8") (pin "P$1") (pinfunction "P$1_P$1") (pintype "bidirectional"))
      (node (ref "R411") (pin "2") (pinfunction "2_2") (pintype "passive"))
    )
    (net (code "143") (name "VCC_3V3") (class "Default")
      (node (ref "C10") (pin "1") (pinfunction "1_1") (pintype "passive"))
      (node (ref "C11") (pin "1") (pinfunction "1_1") (pintype "passive"))
      (node (ref "C12") (pin "1") (pinfunction "1_1") (pintype "passive"))
      (node (ref "C13") (pin "1") (pinfunction "1_1") (pintype "passive"))
      (node (ref "C16") (pin "1") (pinfunction "1_1") (pintype "passive"))
      (node (ref "C20") (pin "1") (pinfunction "1_1") (pintype "passive"))
      (node (ref "C21") (pin "1") (pinfunction "1_1") (pintype "passive"))
      (node (ref "C213") (pin "2") (pinfunction "2_2") (pintype "passive"))
      (node (ref "C214") (pin "2") (pinfunction "2_2") (pintype "passive"))
      (node (ref "C22") (pin "1") (pinfunction "1_1") (pintype "passive"))
      (node (ref "C23") (pin "1") (pinfunction "1_1") (pintype "passive"))
      (node (ref "C25") (pin "2") (pinfunction "2_2") (pintype "passive"))
      (node (ref "C37") (pin "2") (pinfunction "2_2") (pintype "passive"))
      (node (ref "C41") (pin "2") (pinfunction "2_2") (pintype "passive"))
      (node (ref "C42") (pin "2") (pinfunction "2_2") (pintype "passive"))
      (node (ref "C43") (pin "2") (pinfunction "2_2") (pintype "passive"))
      (node (ref "C45") (pin "2") (pinfunction "2_2") (pintype "passive"))
      (node (ref "C46") (pin "1") (pinfunction "1_1") (pintype "passive"))
      (node (ref "C50") (pin "2") (pinfunction "2_2") (pintype "passive"))
      (node (ref "C52") (pin "2") (pinfunction "2_2") (pintype "passive"))
      (node (ref "C64") (pin "2") (pinfunction "2_2") (pintype "passive"))
      (node (ref "C7") (pin "2") (pinfunction "2_2") (pintype "passive"))
      (node (ref "FB3") (pin "1") (pinfunction "1_1") (pintype "passive"))
      (node (ref "FB4") (pin "2") (pinfunction "2_2") (pintype "passive"))
      (node (ref "J14") (pin "P$4") (pinfunction "4VCC_P$4") (pintype "bidirectional"))
      (node (ref "P2") (pin "3") (pinfunction "2_3") (pintype "passive"))
      (node (ref "P3") (pin "P$1") (pinfunction "P$1_P$1") (pintype "bidirectional"))
      (node (ref "Q405") (pin "1") (pinfunction "G_1") (pintype "passive"))
      (node (ref "Q7") (pin "1") (pinfunction "G_1") (pintype "passive"))
      (node (ref "R1") (pin "2") (pinfunction "2_2") (pintype "passive"))
      (node (ref "R107") (pin "2") (pinfunction "2_2") (pintype "passive"))
      (node (ref "R12") (pin "2") (pinfunction "2_2") (pintype "passive"))
      (node (ref "R14") (pin "2") (pinfunction "2_2") (pintype "passive"))
      (node (ref "R16") (pin "1") (pinfunction "1_1") (pintype "passive"))
      (node (ref "R18") (pin "1") (pinfunction "1_1") (pintype "passive"))
      (node (ref "R19") (pin "1") (pinfunction "1_1") (pintype "passive"))
      (node (ref "R301") (pin "1") (pinfunction "1_1") (pintype "passive"))
      (node (ref "R422") (pin "2") (pinfunction "2_2") (pintype "passive"))
      (node (ref "R5") (pin "2") (pinfunction "2_2") (pintype "passive"))
      (node (ref "R57") (pin "2") (pinfunction "2_2") (pintype "passive"))
      (node (ref "R58") (pin "2") (pinfunction "2_2") (pintype "passive"))
      (node (ref "R59") (pin "2") (pinfunction "2_2") (pintype "passive"))
      (node (ref "R61") (pin "2") (pinfunction "2_2") (pintype "passive"))
      (node (ref "R62") (pin "3") (pinfunction "2_3") (pintype "passive"))
      (node (ref "R639") (pin "1") (pinfunction "1_1") (pintype "passive"))
      (node (ref "R84") (pin "1") (pinfunction "1_1") (pintype "passive"))
      (node (ref "R85") (pin "1") (pinfunction "1_1") (pintype "passive"))
      (node (ref "R9") (pin "1") (pinfunction "1_1") (pintype "passive"))
      (node (ref "U1") (pin "P$1") (pinfunction "IOVDD5_P$1") (pintype "power_in"))
      (node (ref "U1") (pin "P$11") (pinfunction "IOVDD4_P$11") (pintype "power_in"))
      (node (ref "U1") (pin "P$20") (pinfunction "IOVDD3_P$20") (pintype "power_in"))
      (node (ref "U1") (pin "P$30") (pinfunction "IOVDD2_P$30") (pintype "power_in"))
      (node (ref "U1") (pin "P$38") (pinfunction "IOVDD1_P$38") (pintype "power_in"))
      (node (ref "U1") (pin "P$44") (pinfunction "ADC_AVDD_P$44") (pintype "power_in"))
      (node (ref "U1") (pin "P$45") (pinfunction "IOVDD0_P$45") (pintype "power_in"))
      (node (ref "U1") (pin "P$49") (pinfunction "VREG_VIN_P$49") (pintype "bidirectional"))
      (node (ref "U1") (pin "P$53") (pinfunction "USB_OTP_VDD_P$53") (pintype "power_in"))
      (node (ref "U1") (pin "P$54") (pinfunction "QSPI_IOVDD_P$54") (pintype "power_in"))
      (node (ref "U11") (pin "8") (pinfunction "8_VCC_8") (pintype "bidirectional"))
      (node (ref "U12") (pin "5") (pinfunction "VDDIO_5") (pintype "power_in"))
      (node (ref "U12") (pin "8") (pinfunction "VDD_8") (pintype "power_in"))
      (node (ref "U123") (pin "5") (pinfunction "VCC_5") (pintype "bidirectional"))
      (node (ref "U2") (pin "P$8") (pinfunction "VDD_P$8") (pintype "bidirectional"))
      (node (ref "U3") (pin "8") (pinfunction "VCC_8") (pintype "bidirectional"))
      (node (ref "U309") (pin "1") (pinfunction "P$1_1") (pintype "bidirectional"))
      (node (ref "U5") (pin "1") (pinfunction "VCC_1") (pintype "bidirectional"))
      (node (ref "U7") (pin "1") (pinfunction "VCC_1") (pintype "bidirectional"))
    )
    (net (code "144") (name "VCC_5V") (class "Default")
      (node (ref "C19") (pin "1") (pinfunction "1_1") (pintype "passive"))
      (node (ref "C33") (pin "2") (pinfunction "2_2") (pintype "passive"))
      (node (ref "C35") (pin "2") (pinfunction "2_2") (pintype "passive"))
      (node (ref "C38") (pin "2") (pinfunction "2_2") (pintype "passive"))
      (node (ref "C39") (pin "2") (pinfunction "2_2") (pintype "passive"))
      (node (ref "C411") (pin "2") (pinfunction "2_2") (pintype "passive"))
      (node (ref "C413") (pin "1") (pinfunction "1_1") (pintype "passive"))
      (node (ref "C66") (pin "1") (pinfunction "1_1") (pintype "passive"))
      (node (ref "FB2") (pin "2") (pinfunction "2_2") (pintype "passive"))
      (node (ref "J2") (pin "2") (pinfunction "H_2") (pintype "bidirectional"))
      (node (ref "J2") (pin "3") (pinfunction "A_3") (pintype "bidirectional"))
      (node (ref "L11") (pin "1") (pinfunction "1_1") (pintype "bidirectional"))
      (node (ref "P7") (pin "P$1") (pinfunction "P$1_P$1") (pintype "bidirectional"))
      (node (ref "R20") (pin "1") (pinfunction "1_1") (pintype "passive"))
      (node (ref "R23") (pin "1") (pinfunction "1_1") (pintype "passive"))
      (node (ref "R283") (pin "1") (pinfunction "1_1") (pintype "passive"))
      (node (ref "R303") (pin "1") (pinfunction "1_1") (pintype "passive"))
      (node (ref "R63") (pin "2") (pinfunction "2_2") (pintype "passive"))
      (node (ref "R7") (pin "1") (pinfunction "1_1") (pintype "passive"))
      (node (ref "U30") (pin "5") (pinfunction "IN_5") (pintype "bidirectional"))
      (node (ref "U401") (pin "P$1") (pinfunction "1_VIN_P$1") (pintype "bidirectional"))
      (node (ref "U6") (pin "1") (pinfunction "VCC_1") (pintype "power_in"))
    )
    (net (code "145") (name "VCC_5V_SERVO") (class "Default")
      (node (ref "C31") (pin "+") (pinfunction "+_+") (pintype "passive"))
      (node (ref "C58") (pin "2") (pinfunction "2_2") (pintype "passive"))
      (node (ref "C59") (pin "2") (pinfunction "2_2") (pintype "passive"))
      (node (ref "C6") (pin "2") (pinfunction "2_2") (pintype "passive"))
      (node (ref "C60") (pin "2") (pinfunction "2_2") (pintype "passive"))
      (node (ref "D10") (pin "C") (pinfunction "C_C") (pintype "passive"))
      (node (ref "D3") (pin "-") (pinfunction "-_-") (pintype "passive"))
      (node (ref "J1") (pin "3") (pinfunction "3_3") (pintype "bidirectional"))
      (node (ref "J15") (pin "2") (pinfunction "V_2") (pintype "bidirectional"))
      (node (ref "P10") (pin "P$1") (pinfunction "P$1_P$1") (pintype "bidirectional"))
      (node (ref "R30") (pin "1") (pinfunction "1_1") (pintype "passive"))
      (node (ref "R423") (pin "1") (pinfunction "1_1") (pintype "passive"))
    )
    (net (code "146") (name "VCC_IO_RGB") (class "Default")
      (node (ref "C183") (pin "1") (pinfunction "1_1") (pintype "passive"))
      (node (ref "C8") (pin "1") (pinfunction "1_1") (pintype "passive"))
      (node (ref "L2") (pin "2") (pinfunction "2_2") (pintype "bidirectional"))
      (node (ref "P69") (pin "P$1") (pinfunction "P$1_P$1") (pintype "bidirectional"))
      (node (ref "R116") (pin "2") (pinfunction "2_2") (pintype "passive"))
      (node (ref "R118") (pin "1") (pinfunction "1_1") (pintype "passive"))
      (node (ref "R76") (pin "2") (pinfunction "2_2") (pintype "passive"))
      (node (ref "U34") (pin "5") (pinfunction "5_VIN_5") (pintype "bidirectional"))
    )
    (net (code "147") (name "XIN") (class "Default")
      (node (ref "C1") (pin "2") (pinfunction "2_2") (pintype "passive"))
      (node (ref "U1") (pin "P$21") (pinfunction "XIN_P$21") (pintype "bidirectional"))
      (node (ref "X1") (pin "1") (pinfunction "XIN_1") (pintype "bidirectional"))
    )
    (net (code "148") (name "XOUT") (class "Default")
      (node (ref "R8") (pin "1") (pinfunction "1_1") (pintype "passive"))
      (node (ref "U1") (pin "P$22") (pinfunction "XOUT_P$22") (pintype "bidirectional"))
    )
    (net (code "149") (name "unconnected-(BOOT-2-PadP$2)") (class "Default")
      (node (ref "BOOT") (pin "P$2") (pinfunction "2_P$2") (pintype "bidirectional"))
    )
    (net (code "150") (name "unconnected-(BOOT-3-PadP$3)") (class "Default")
      (node (ref "BOOT") (pin "P$3") (pinfunction "3_P$3") (pintype "bidirectional"))
    )
    (net (code "151") (name "unconnected-(D033-2_DOUT-Pad2)") (class "Default")
      (node (ref "D033") (pin "2") (pinfunction "2_DOUT_2") (pintype "bidirectional"))
    )
    (net (code "152") (name "unconnected-(FPC1-NC-PadP$8)") (class "Default")
      (node (ref "FPC1") (pin "P$8") (pinfunction "NC_P$8") (pintype "bidirectional"))
    )
    (net (code "153") (name "unconnected-(J1-Pad2)") (class "Default")
      (node (ref "J1") (pin "2") (pinfunction "2_2") (pintype "bidirectional"))
    )
    (net (code "154") (name "unconnected-(J2-A-Pad1)") (class "Default")
      (node (ref "J2") (pin "1") (pinfunction "A_1") (pintype "bidirectional"))
    )
    (net (code "155") (name "unconnected-(J110-3_2A-Pad3)") (class "Default")
      (node (ref "J110") (pin "3") (pinfunction "3_2A_3") (pintype "bidirectional"))
    )
    (net (code "156") (name "unconnected-(J110-4_1A-Pad4)") (class "Default")
      (node (ref "J110") (pin "4") (pinfunction "4_1A_4") (pintype "bidirectional"))
    )
    (net (code "157") (name "unconnected-(J110-6_1B-Pad6)") (class "Default")
      (node (ref "J110") (pin "6") (pinfunction "6_1B_6") (pintype "bidirectional"))
    )
    (net (code "158") (name "unconnected-(RESET-1-PadP$1)") (class "Default")
      (node (ref "RESET") (pin "P$1") (pinfunction "1_P$1") (pintype "bidirectional"))
    )
    (net (code "159") (name "unconnected-(RESET-4-PadP$4)") (class "Default")
      (node (ref "RESET") (pin "P$4") (pinfunction "4_P$4") (pintype "bidirectional"))
    )
    (net (code "160") (name "unconnected-(U8-NC-Pad6)") (class "Default")
      (node (ref "U8") (pin "6") (pinfunction "NC_6") (pintype "bidirectional"))
    )
    (net (code "161") (name "unconnected-(U11-5_IN2+-Pad5)") (class "Default")
      (node (ref "U11") (pin "5") (pinfunction "5_IN2+_5") (pintype "bidirectional"))
    )
    (net (code "162") (name "unconnected-(U11-6_IN2--Pad6)") (class "Default")
      (node (ref "U11") (pin "6") (pinfunction "6_IN2-_6") (pintype "bidirectional"))
    )
    (net (code "163") (name "unconnected-(U11-7_OUT2-Pad7)") (class "Default")
      (node (ref "U11") (pin "7") (pinfunction "7_OUT2_7") (pintype "bidirectional"))
    )
    (net (code "164") (name "unconnected-(U12-INT1-Pad4)") (class "Default")
      (node (ref "U12") (pin "4") (pinfunction "INT1_4") (pintype "bidirectional"))
    )
    (net (code "165") (name "unconnected-(U12-INT2-Pad9)") (class "Default")
      (node (ref "U12") (pin "9") (pinfunction "INT2_9") (pintype "bidirectional"))
    )
  )
)
